# STM32F429_MAIN.net
KiCad netlist of a schematic drawn in Altium Designer
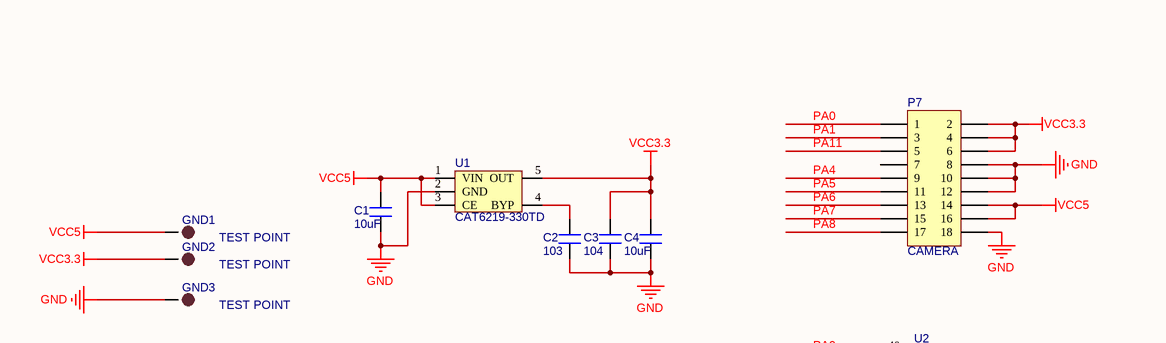
[diagram p0: STM32F429_MAIN.SchDoc, top left]
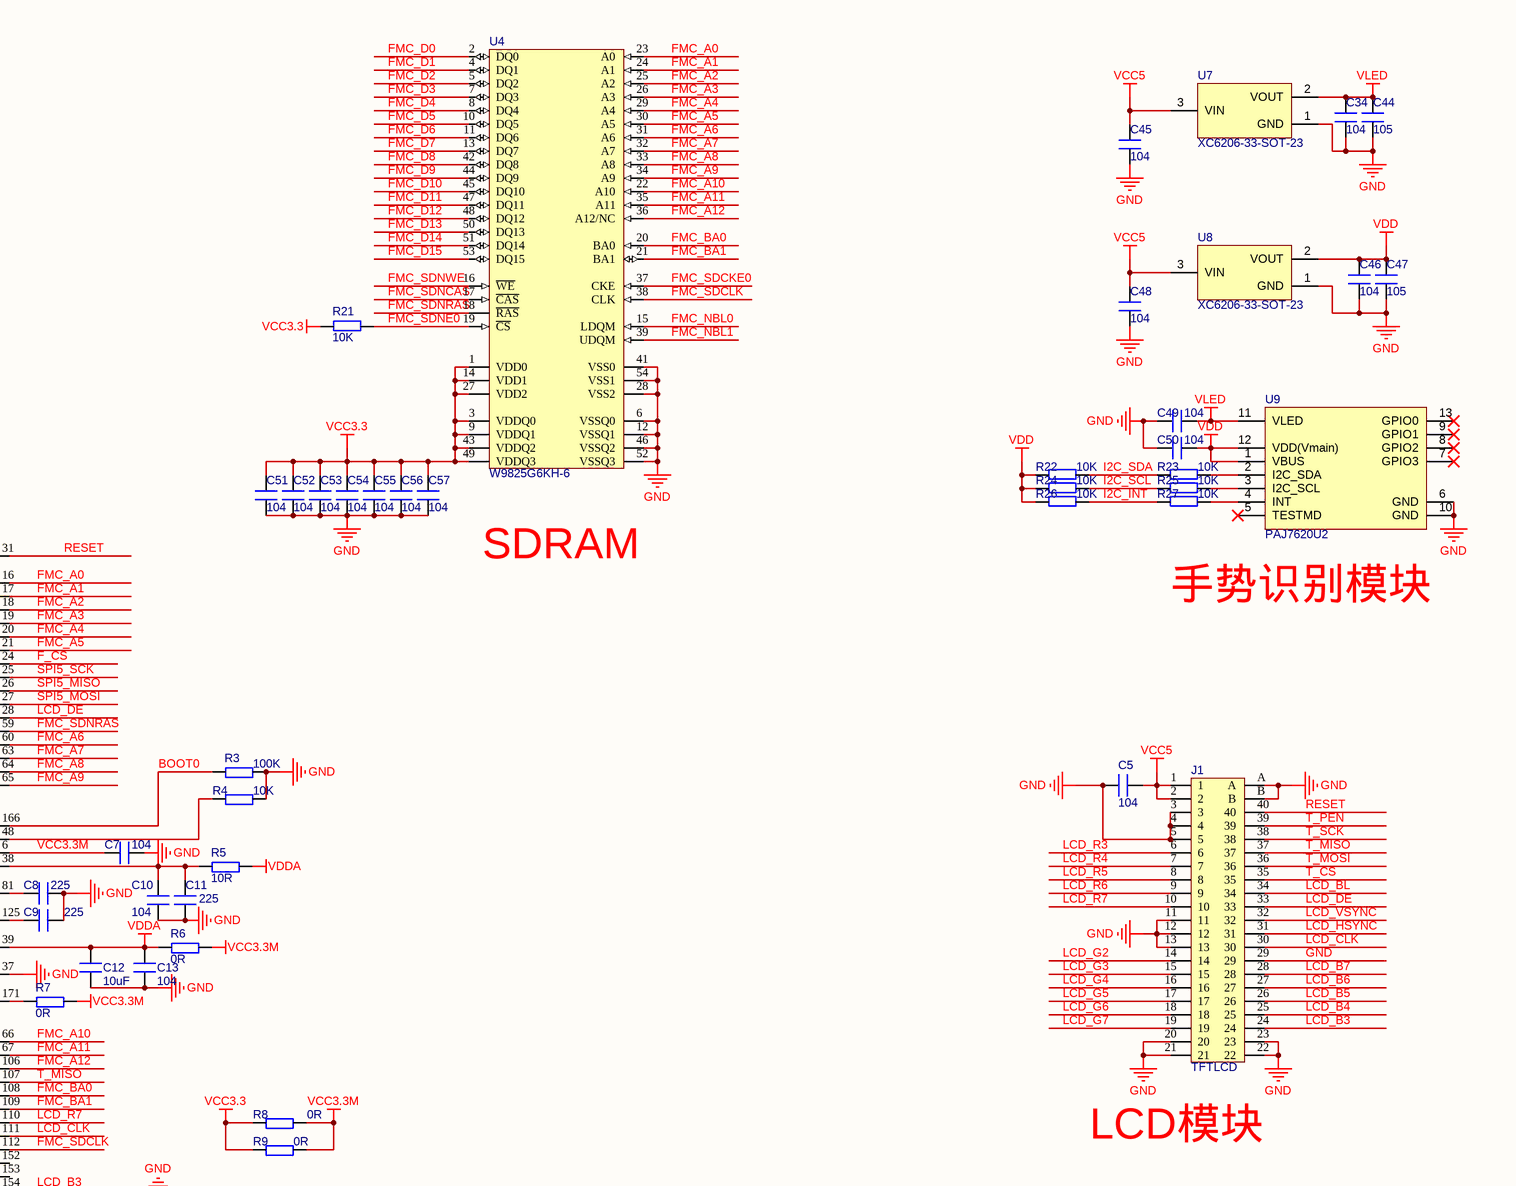
[diagram p1: STM32F429_MAIN.SchDoc, top right]
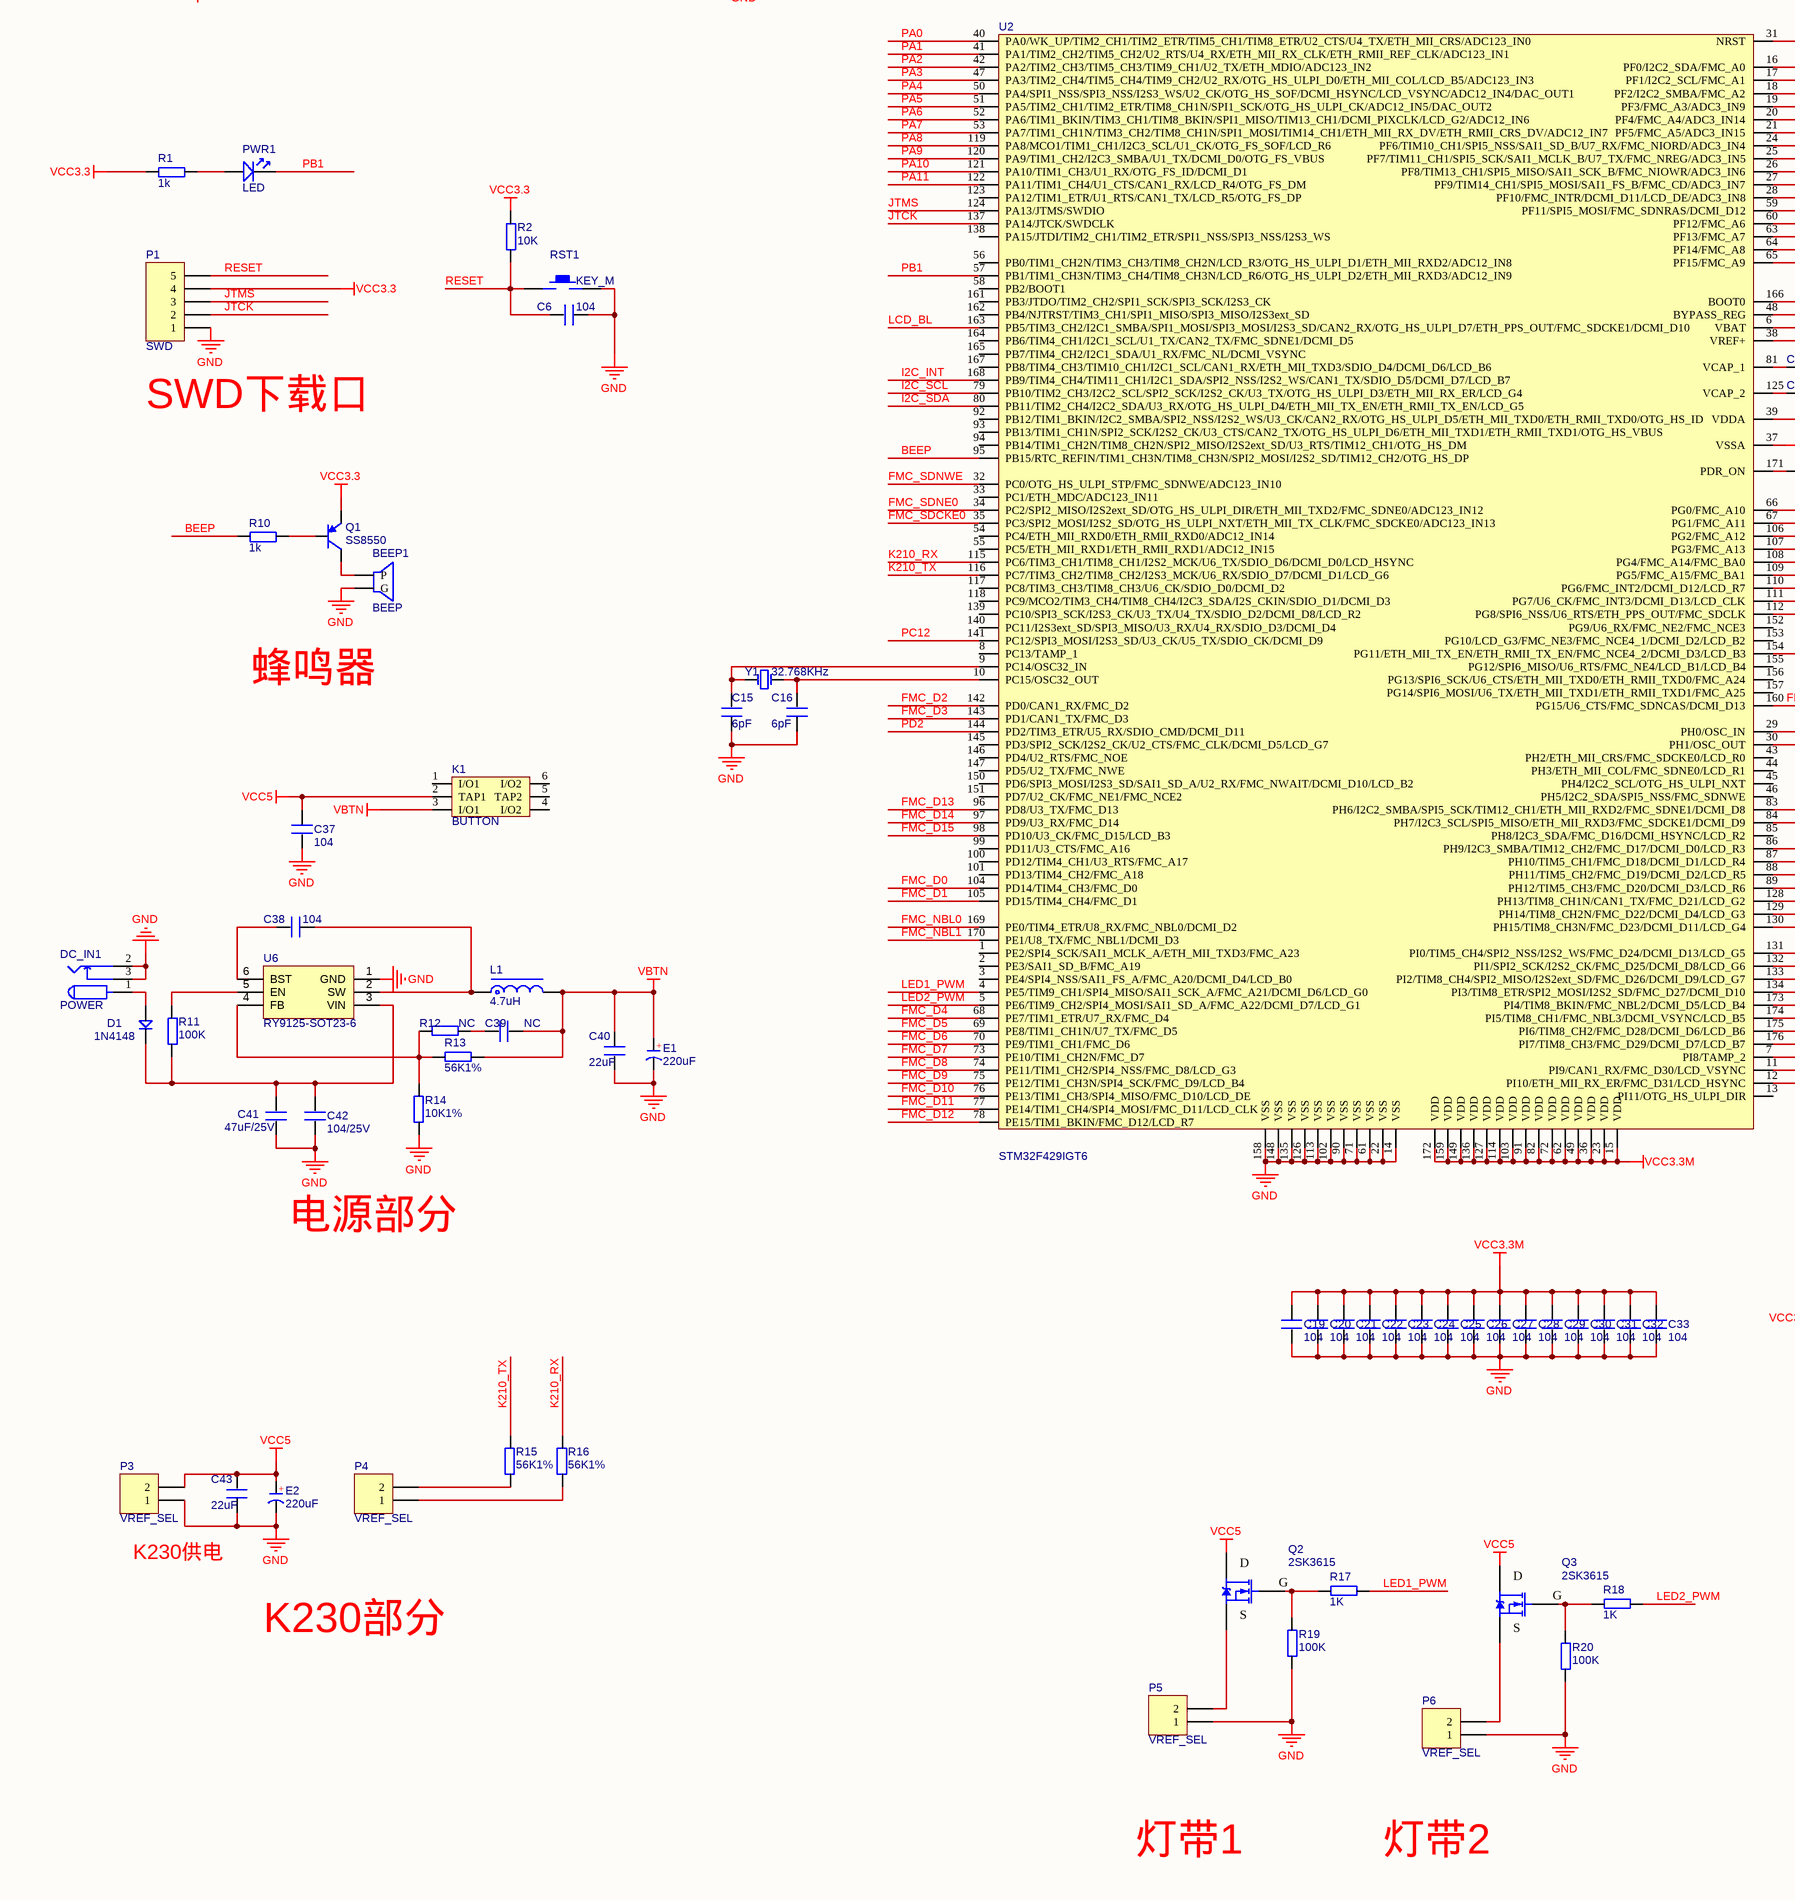
[diagram p2: STM32F429_MAIN.SchDoc, bottom left]
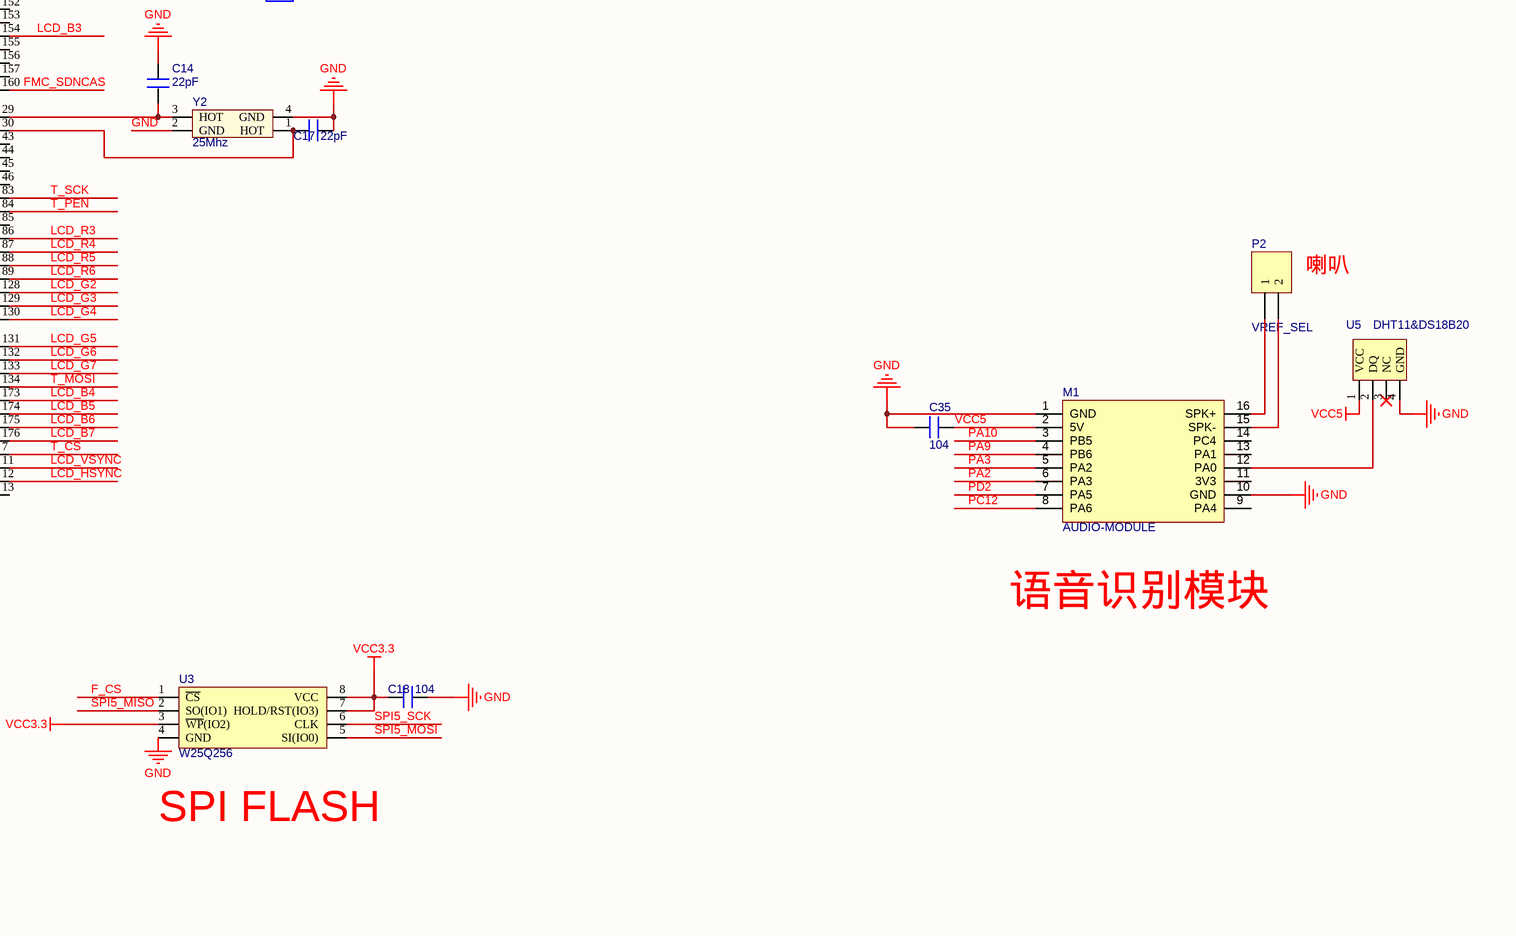
[diagram p3: STM32F429_MAIN.SchDoc, bottom right]

(export (version "E")
  (design (tool "Eeschema 10.0.6"))
  (components
    (comp (ref "BEEP1")
      (value "BEEP")
      (footprint "BELL-5")
      (libsource (lib "阿波罗STM32F4&F7底板封装库") (part "BEEP"))
    )
    (comp (ref "C1") (value "10uF") (footprint "0402") (libsource (lib "STM32F429核心板封装库") (part "C")))
    (comp (ref "C2") (value "103") (footprint "0402") (libsource (lib "STM32F429核心板封装库") (part "C")))
    (comp (ref "C3") (value "104") (footprint "0402") (libsource (lib "STM32F429核心板封装库") (part "C")))
    (comp (ref "C4") (value "10uF") (footprint "0402") (libsource (lib "STM32F429核心板封装库") (part "C")))
    (comp (ref "C5") (value "104") (footprint "0603P") (libsource (lib "ATK-4342 4.3寸RGB屏模块封装库") (part "C")))
    (comp (ref "C6") (value "104") (footprint "0402") (libsource (lib "STM32F429核心板封装库") (part "C")))
    (comp (ref "C7") (value "104") (footprint "0402") (libsource (lib "STM32F429核心板封装库") (part "C")))
    (comp (ref "C8") (value "225") (footprint "0402") (libsource (lib "STM32F429核心板封装库") (part "C")))
    (comp (ref "C9") (value "225") (footprint "0402") (libsource (lib "STM32F429核心板封装库") (part "C")))
    (comp (ref "C10") (value "104") (footprint "0402") (libsource (lib "STM32F429核心板封装库") (part "C")))
    (comp (ref "C11") (value "225") (footprint "0402") (libsource (lib "STM32F429核心板封装库") (part "C")))
    (comp (ref "C12") (value "10uF") (footprint "0402") (libsource (lib "STM32F429核心板封装库") (part "C")))
    (comp (ref "C13") (value "104") (footprint "0402") (libsource (lib "STM32F429核心板封装库") (part "C")))
    (comp (ref "C14") (value "22pF") (footprint "0402") (libsource (lib "STM32F429核心板封装库") (part "C")))
    (comp (ref "C15") (value "6pF") (footprint "0402") (libsource (lib "STM32F429核心板封装库") (part "C")))
    (comp (ref "C16") (value "6pF") (footprint "0402") (libsource (lib "STM32F429核心板封装库") (part "C")))
    (comp (ref "C17") (value "22pF") (footprint "0402") (libsource (lib "STM32F429核心板封装库") (part "C")))
    (comp (ref "C18") (value "104") (footprint "0402") (libsource (lib "STM32F429核心板封装库") (part "C")))
    (comp (ref "C19") (value "104") (footprint "0402") (libsource (lib "STM32F429核心板封装库") (part "C")))
    (comp (ref "C20") (value "104") (footprint "0402") (libsource (lib "STM32F429核心板封装库") (part "C")))
    (comp (ref "C21") (value "104") (footprint "0402") (libsource (lib "STM32F429核心板封装库") (part "C")))
    (comp (ref "C22") (value "104") (footprint "0402") (libsource (lib "STM32F429核心板封装库") (part "C")))
    (comp (ref "C23") (value "104") (footprint "0402") (libsource (lib "STM32F429核心板封装库") (part "C")))
    (comp (ref "C24") (value "104") (footprint "0402") (libsource (lib "STM32F429核心板封装库") (part "C")))
    (comp (ref "C25") (value "104") (footprint "0402") (libsource (lib "STM32F429核心板封装库") (part "C")))
    (comp (ref "C26") (value "104") (footprint "0402") (libsource (lib "STM32F429核心板封装库") (part "C")))
    (comp (ref "C27") (value "104") (footprint "0402") (libsource (lib "STM32F429核心板封装库") (part "C")))
    (comp (ref "C28") (value "104") (footprint "0402") (libsource (lib "STM32F429核心板封装库") (part "C")))
    (comp (ref "C29") (value "104") (footprint "0402") (libsource (lib "STM32F429核心板封装库") (part "C")))
    (comp (ref "C30") (value "104") (footprint "0402") (libsource (lib "STM32F429核心板封装库") (part "C")))
    (comp (ref "C31") (value "104") (footprint "0402") (libsource (lib "STM32F429核心板封装库") (part "C")))
    (comp (ref "C32") (value "104") (footprint "0402") (libsource (lib "STM32F429核心板封装库") (part "C")))
    (comp (ref "C33") (value "104") (footprint "0402") (libsource (lib "STM32F429核心板封装库") (part "C")))
    (comp (ref "C34") (value "104") (footprint "0603P") (libsource (lib "ATK-4342 4.3寸RGB屏模块封装库") (part "C")))
    (comp (ref "C35") (value "104") (footprint "0603P") (libsource (lib "ATK-4342 4.3寸RGB屏模块封装库") (part "C")))
    (comp (ref "C37") (value "104") (footprint "0402") (libsource (lib "STM32F429核心板封装库") (part "C")))
    (comp (ref "C38") (value "104") (footprint "0805") (libsource (lib "STM32F429核心板封装库") (part "C")))
    (comp (ref "C39") (value "NC") (footprint "0603P") (libsource (lib "STM32F429核心板封装库") (part "C")))
    (comp (ref "C40") (value "22uF") (footprint "C 1206_L") (libsource (lib "STM32F429核心板封装库") (part "C")))
    (comp (ref "C41") (value "47uF/25V") (footprint "0805") (libsource (lib "STM32F429核心板封装库") (part "C")))
    (comp (ref "C42") (value "104/25V") (footprint "0805") (libsource (lib "STM32F429核心板封装库") (part "C")))
    (comp (ref "C43") (value "22uF") (footprint "0402") (libsource (lib "STM32F429核心板封装库") (part "C")))
    (comp (ref "C44") (value "105") (footprint "0603P") (libsource (lib "ATK-4342 4.3寸RGB屏模块封装库") (part "C")))
    (comp (ref "C45") (value "104") (footprint "0603P") (libsource (lib "ATK-4342 4.3寸RGB屏模块封装库") (part "C")))
    (comp (ref "C46") (value "104") (footprint "0603P") (libsource (lib "ATK-4342 4.3寸RGB屏模块封装库") (part "C")))
    (comp (ref "C47") (value "105") (footprint "0603P") (libsource (lib "ATK-4342 4.3寸RGB屏模块封装库") (part "C")))
    (comp (ref "C48") (value "104") (footprint "0603P") (libsource (lib "ATK-4342 4.3寸RGB屏模块封装库") (part "C")))
    (comp (ref "C49") (value "104") (footprint "0603P") (libsource (lib "ATK-4342 4.3寸RGB屏模块封装库") (part "C")))
    (comp (ref "C50") (value "104") (footprint "0603P") (libsource (lib "ATK-4342 4.3寸RGB屏模块封装库") (part "C")))
    (comp (ref "C51") (value "104") (footprint "0603P") (libsource (lib "ATK-4342 4.3寸RGB屏模块封装库") (part "C")))
    (comp (ref "C52") (value "104") (footprint "0603P") (libsource (lib "ATK-4342 4.3寸RGB屏模块封装库") (part "C")))
    (comp (ref "C53") (value "104") (footprint "0603P") (libsource (lib "ATK-4342 4.3寸RGB屏模块封装库") (part "C")))
    (comp (ref "C54") (value "104") (footprint "0603P") (libsource (lib "ATK-4342 4.3寸RGB屏模块封装库") (part "C")))
    (comp (ref "C55") (value "104") (footprint "0603P") (libsource (lib "ATK-4342 4.3寸RGB屏模块封装库") (part "C")))
    (comp (ref "C56") (value "104") (footprint "0603P") (libsource (lib "ATK-4342 4.3寸RGB屏模块封装库") (part "C")))
    (comp (ref "C57") (value "104") (footprint "0603P") (libsource (lib "ATK-4342 4.3寸RGB屏模块封装库") (part "C")))
    (comp (ref "D1")
      (value "1N4148")
      (footprint "DIODE_SOP")
      (libsource (lib "阿波罗STM32F4&F7底板封装库") (part "D"))
    )
    (comp (ref "DC_IN1")
      (value "POWER")
      (footprint "DC10B")
      (libsource (lib "阿波罗STM32F4&F7底板封装库") (part "POW"))
    )
    (comp (ref "E1")
      (value "220uF")
      (footprint "CM A(3*5.4)")
      (description "贴片电解电容")
      (fields (field (name "版权归属") "源创客"))
      (libsource (lib "Basic") (part "C-CM"))
    )
    (comp (ref "E2")
      (value "220uF")
      (footprint "CM A(3*5.4)")
      (description "贴片电解电容")
      (fields (field (name "版权归属") "源创客"))
      (libsource (lib "Basic") (part "C-CM"))
    )
    (comp (ref "GND1")
      (value "TEST POINT")
      (footprint "TP-1.5")
      (description "测试点")
      (libsource (lib "STM32F429核心板封装库") (part "TEST-POINT"))
    )
    (comp (ref "GND2")
      (value "TEST POINT")
      (footprint "TP-1.5")
      (description "测试点")
      (libsource (lib "STM32F429核心板封装库") (part "TEST-POINT"))
    )
    (comp (ref "GND3")
      (value "TEST POINT")
      (footprint "TP-1.5")
      (description "测试点")
      (libsource (lib "STM32F429核心板封装库") (part "TEST-POINT"))
    )
    (comp (ref "J1")
      (value "TFTLCD")
      (footprint "FPC-TOP40")
      (description "FPC-40P-0.5mm")
      (libsource (lib "ATK-4342 4.3寸RGB屏模块封装库") (part "FPC-40"))
    )
    (comp (ref "K1")
      (value "BUTTON")
      (footprint "BTN8.5*8.5")
      (libsource (lib "阿波罗STM32F4&F7底板封装库") (part "BUTTON"))
    )
    (comp (ref "L1")
      (value "4.7uH")
      (footprint "CD31")
      (description "贴片功率电感")
      (fields (field (name "版权归属") "源创客"))
      (libsource (lib "Basic") (part "L-CD"))
    )
    (comp (ref "M1")
      (value "AUDIO-MODULE")
      (footprint "AI_audio")
      (libsource (lib "智能导航仪") (part "ai_audio"))
    )
    (comp (ref "P1")
      (value "SWD")
      (footprint "HDR1X5")
      (description "Header, 5-Pin")
      (fields (field (name "PUBLISHER") "Altium Limited"))
      (libsource (lib "STM32F429核心板封装库") (part "Header 5"))
    )
    (comp (ref "P2")
      (value "VREF_SEL")
      (footprint "HDR1X2")
      (description "Header, 2-Pin")
      (fields (field (name "PUBLISHER") "Altium Limited"))
      (libsource (lib "") (part "Header 2_1"))
    )
    (comp (ref "P3")
      (value "VREF_SEL")
      (footprint "HDR1X2")
      (description "Header, 2-Pin")
      (fields (field (name "PUBLISHER") "Altium Limited"))
      (libsource (lib "阿波罗STM32F4&F7底板封装库") (part "Header 2"))
    )
    (comp (ref "P4")
      (value "VREF_SEL")
      (footprint "HDR1X2")
      (description "Header, 2-Pin")
      (fields (field (name "PUBLISHER") "Altium Limited"))
      (libsource (lib "阿波罗STM32F4&F7底板封装库") (part "Header 2"))
    )
    (comp (ref "P5")
      (value "VREF_SEL")
      (footprint "HDR1X2")
      (description "Header, 2-Pin")
      (fields (field (name "PUBLISHER") "Altium Limited"))
      (libsource (lib "阿波罗STM32F4&F7底板封装库") (part "Header 2"))
    )
    (comp (ref "P6")
      (value "VREF_SEL")
      (footprint "HDR1X2")
      (description "Header, 2-Pin")
      (fields (field (name "PUBLISHER") "Altium Limited"))
      (libsource (lib "阿波罗STM32F4&F7底板封装库") (part "Header 2"))
    )
    (comp (ref "P7")
      (value "CAMERA")
      (footprint "HDR2X9")
      (description "Header, 9-Pin, Dual row")
      (fields (field (name "PUBLISHER") "Altium Limited"))
      (libsource (lib "阿波罗STM32F4&F7底板封装库") (part "Header 9X2"))
    )
    (comp (ref "PWR1")
      (value "LED")
      (footprint "SMDLED-0603")
      (libsource (lib "STM32F429核心板封装库") (part "LED"))
    )
    (comp (ref "Q1")
      (value "SS8550")
      (footprint "SOT23-3N")
      (description "高频放大-PNP型")
      (fields (field (name "版权归属") "源创客"))
      (libsource (lib "Basic") (part "8550-SMD"))
    )
    (comp (ref "Q2")
      (value "2SK3615")
      (footprint "TO252")
      (description "N沟场效应管")
      (fields (field (name "版权归属") "源创客"))
      (libsource (lib "Basic") (part "2SK3615"))
    )
    (comp (ref "Q3")
      (value "2SK3615")
      (footprint "TO252")
      (description "N沟场效应管")
      (fields (field (name "版权归属") "源创客"))
      (libsource (lib "Basic") (part "2SK3615"))
    )
    (comp (ref "R1") (value "1k") (footprint "0402") (libsource (lib "STM32F429核心板封装库") (part "R")))
    (comp (ref "R2") (value "10K") (footprint "0402") (libsource (lib "STM32F429核心板封装库") (part "R")))
    (comp (ref "R3") (value "100K") (footprint "0402") (libsource (lib "STM32F429核心板封装库") (part "R")))
    (comp (ref "R4") (value "10K") (footprint "0402") (libsource (lib "STM32F429核心板封装库") (part "R")))
    (comp (ref "R5") (value "10R") (footprint "0402") (libsource (lib "STM32F429核心板封装库") (part "R")))
    (comp (ref "R6") (value "0R") (footprint "0402") (libsource (lib "STM32F429核心板封装库") (part "R")))
    (comp (ref "R7") (value "0R") (footprint "0402") (libsource (lib "STM32F429核心板封装库") (part "R")))
    (comp (ref "R8") (value "0R") (footprint "0402") (libsource (lib "STM32F429核心板封装库") (part "R")))
    (comp (ref "R9") (value "0R") (footprint "0402") (libsource (lib "STM32F429核心板封装库") (part "R")))
    (comp (ref "R10") (value "1k") (footprint "0402") (libsource (lib "STM32F429核心板封装库") (part "R")))
    (comp (ref "R11") (value "100K") (footprint "0603P") (libsource (lib "STM32F429核心板封装库") (part "R")))
    (comp (ref "R12") (value "NC") (footprint "0603P") (libsource (lib "STM32F429核心板封装库") (part "R")))
    (comp (ref "R13") (value "56K1%") (footprint "0603P") (libsource (lib "STM32F429核心板封装库") (part "R")))
    (comp (ref "R14") (value "10K1%") (footprint "0603P") (libsource (lib "STM32F429核心板封装库") (part "R")))
    (comp (ref "R15") (value "56K1%") (footprint "0402") (libsource (lib "STM32F429核心板封装库") (part "R")))
    (comp (ref "R16") (value "56K1%") (footprint "0402") (libsource (lib "STM32F429核心板封装库") (part "R")))
    (comp (ref "R17") (value "1K") (footprint "0603P") (libsource (lib "STM32F429核心板封装库") (part "R")))
    (comp (ref "R18") (value "1K") (footprint "0603P") (libsource (lib "STM32F429核心板封装库") (part "R")))
    (comp (ref "R19") (value "100K") (footprint "0603P") (libsource (lib "STM32F429核心板封装库") (part "R")))
    (comp (ref "R20") (value "100K") (footprint "0603P") (libsource (lib "STM32F429核心板封装库") (part "R")))
    (comp (ref "R21") (value "10K") (footprint "0402") (libsource (lib "STM32F429核心板封装库") (part "R")))
    (comp (ref "R22") (value "10K") (footprint "0402") (libsource (lib "STM32F429核心板封装库") (part "R")))
    (comp (ref "R23") (value "10K") (footprint "0402") (libsource (lib "STM32F429核心板封装库") (part "R")))
    (comp (ref "R24") (value "10K") (footprint "0402") (libsource (lib "STM32F429核心板封装库") (part "R")))
    (comp (ref "R25") (value "10K") (footprint "0402") (libsource (lib "STM32F429核心板封装库") (part "R")))
    (comp (ref "R26") (value "10K") (footprint "0402") (libsource (lib "STM32F429核心板封装库") (part "R")))
    (comp (ref "R27") (value "10K") (footprint "0402") (libsource (lib "STM32F429核心板封装库") (part "R")))
    (comp (ref "RST1")
      (value "KEY_M")
      (footprint "KEY_SOP3625")
      (libsource (lib "STM32F429核心板封装库") (part "KEY_M"))
    )
    (comp (ref "U1")
      (value "CAT6219-330TD")
      (footprint "SOT-23-5")
      (description "3.3V 500mA LDO")
      (libsource (lib "STM32F429核心板封装库") (part "CAT6219-330TD"))
    )
    (comp (ref "U2")
      (value "STM32F429IGT6")
      (footprint "LQFP176")
      (libsource (lib "STM32F429核心板封装库") (part "STM32F429IGT6"))
    )
    (comp (ref "U3")
      (value "W25Q256")
      (footprint "WSON8")
      (description "W25Q128")
      (libsource (lib "STM32F429核心板封装库") (part "W25Q128"))
    )
    (comp (ref "U4")
      (value "W9825G6KH-6")
      (footprint "TSOP54")
      (description "32MB SDRAM")
      (libsource (lib "STM32F429核心板封装库") (part "IS42S16160B"))
    )
    (comp (ref "U5")
      (value "DHT11&DS18B20")
      (footprint "DHT11")
      (description "数字温湿度传感器")
      (libsource (lib "阿波罗STM32F4&F7底板封装库") (part "DHT11"))
    )
    (comp (ref "U6") (value "RY9125-SOT23-6") (footprint "SOT23-6") (libsource (lib "智能导航仪") (part "RY9125")))
    (comp (ref "U7")
      (value "XC6206-33-SOT-23")
      (footprint "SOT-23")
      (libsource (lib "智能导航仪") (part "XC6206-33"))
    )
    (comp (ref "U8")
      (value "XC6206-33-SOT-23")
      (footprint "SOT-23")
      (libsource (lib "智能导航仪") (part "XC6206-33"))
    )
    (comp (ref "U9") (value "PAJ7620U2") (footprint "PAJ7620U2") (libsource (lib "智能导航仪") (part "PAJ7620U2")))
    (comp (ref "Y1")
      (value "32.768KHz")
      (footprint "XTAL3215")
      (description "普通晶振")
      (fields (field (name "PUBLISHER") "Altium Limited"))
      (libsource (lib "STM32F429核心板封装库") (part "XTAL"))
    )
    (comp (ref "Y2")
      (value "25Mhz")
      (footprint "XTAL3225")
      (description "3225贴片无源晶振")
      (libsource (lib "STM32F429核心板封装库") (part "XTAL_3225"))
    )
  )
  (nets
    (net (code "1") (name "/BEEP") (class "Default")
      (node (ref "R10") (pin "1") (pintype "passive"))
      (node (ref "U2") (pin "95") (pinfunction "PB15/RTC_REFIN/TIM1_CH3N/TIM8_CH3N/SPI2_MOSI/I2S2_SD/TIM12_CH2/OTG_HS_DP_95") (pintype "passive"))
    )
    (net (code "2") (name "/BOOT0") (class "Default")
      (node (ref "R3") (pin "1") (pintype "passive"))
      (node (ref "U2") (pin "166") (pinfunction "BOOT0_166") (pintype "passive"))
    )
    (net (code "3") (name "/FMC_A0") (class "Default")
      (node (ref "U2") (pin "16") (pinfunction "PF0/I2C2_SDA/FMC_A0_16") (pintype "passive"))
      (node (ref "U4") (pin "23") (pinfunction "A0_23") (pintype "input"))
    )
    (net (code "4") (name "/FMC_A1") (class "Default")
      (node (ref "U2") (pin "17") (pinfunction "PF1/I2C2_SCL/FMC_A1_17") (pintype "passive"))
      (node (ref "U4") (pin "24") (pinfunction "A1_24") (pintype "input"))
    )
    (net (code "5") (name "/FMC_A2") (class "Default")
      (node (ref "U2") (pin "18") (pinfunction "PF2/I2C2_SMBA/FMC_A2_18") (pintype "passive"))
      (node (ref "U4") (pin "25") (pinfunction "A2_25") (pintype "input"))
    )
    (net (code "6") (name "/FMC_A3") (class "Default")
      (node (ref "U2") (pin "19") (pinfunction "PF3/FMC_A3/ADC3_IN9_19") (pintype "passive"))
      (node (ref "U4") (pin "26") (pinfunction "A3_26") (pintype "input"))
    )
    (net (code "7") (name "/FMC_A4") (class "Default")
      (node (ref "U2") (pin "20") (pinfunction "PF4/FMC_A4/ADC3_IN14_20") (pintype "passive"))
      (node (ref "U4") (pin "29") (pinfunction "A4_29") (pintype "input"))
    )
    (net (code "8") (name "/FMC_A5") (class "Default")
      (node (ref "U2") (pin "21") (pinfunction "PF5/FMC_A5/ADC3_IN15_21") (pintype "passive"))
      (node (ref "U4") (pin "30") (pinfunction "A5_30") (pintype "input"))
    )
    (net (code "9") (name "/FMC_A6") (class "Default")
      (node (ref "U2") (pin "60") (pinfunction "PF12/FMC_A6_60") (pintype "passive"))
      (node (ref "U4") (pin "31") (pinfunction "A6_31") (pintype "input"))
    )
    (net (code "10") (name "/FMC_A7") (class "Default")
      (node (ref "U2") (pin "63") (pinfunction "PF13/FMC_A7_63") (pintype "passive"))
      (node (ref "U4") (pin "32") (pinfunction "A7_32") (pintype "input"))
    )
    (net (code "11") (name "/FMC_A8") (class "Default")
      (node (ref "U2") (pin "64") (pinfunction "PF14/FMC_A8_64") (pintype "passive"))
      (node (ref "U4") (pin "33") (pinfunction "A8_33") (pintype "input"))
    )
    (net (code "12") (name "/FMC_A9") (class "Default")
      (node (ref "U2") (pin "65") (pinfunction "PF15/FMC_A9_65") (pintype "passive"))
      (node (ref "U4") (pin "34") (pinfunction "A9_34") (pintype "input"))
    )
    (net (code "13") (name "/FMC_A10") (class "Default")
      (node (ref "U2") (pin "66") (pinfunction "PG0/FMC_A10_66") (pintype "passive"))
      (node (ref "U4") (pin "22") (pinfunction "A10_22") (pintype "input"))
    )
    (net (code "14") (name "/FMC_A11") (class "Default")
      (node (ref "U2") (pin "67") (pinfunction "PG1/FMC_A11_67") (pintype "passive"))
      (node (ref "U4") (pin "35") (pinfunction "A11_35") (pintype "input"))
    )
    (net (code "15") (name "/FMC_A12") (class "Default")
      (node (ref "U2") (pin "106") (pinfunction "PG2/FMC_A12_106") (pintype "passive"))
      (node (ref "U4") (pin "36") (pinfunction "A12/NC_36") (pintype "input"))
    )
    (net (code "16") (name "/FMC_BA0") (class "Default")
      (node (ref "U2") (pin "108") (pinfunction "PG4/FMC_A14/FMC_BA0_108") (pintype "passive"))
      (node (ref "U4") (pin "20") (pinfunction "BA0_20") (pintype "input"))
    )
    (net (code "17") (name "/FMC_BA1") (class "Default")
      (node (ref "U2") (pin "109") (pinfunction "PG5/FMC_A15/FMC_BA1_109") (pintype "passive"))
      (node (ref "U4") (pin "21") (pinfunction "BA1_21") (pintype "bidirectional"))
    )
    (net (code "18") (name "/FMC_D0") (class "Default")
      (node (ref "U2") (pin "104") (pinfunction "PD14/TIM4_CH3/FMC_D0_104") (pintype "passive"))
      (node (ref "U4") (pin "2") (pinfunction "DQ0_2") (pintype "bidirectional"))
    )
    (net (code "19") (name "/FMC_D1") (class "Default")
      (node (ref "U2") (pin "105") (pinfunction "PD15/TIM4_CH4/FMC_D1_105") (pintype "passive"))
      (node (ref "U4") (pin "4") (pinfunction "DQ1_4") (pintype "bidirectional"))
    )
    (net (code "20") (name "/FMC_D2") (class "Default")
      (node (ref "U2") (pin "142") (pinfunction "PD0/CAN1_RX/FMC_D2_142") (pintype "passive"))
      (node (ref "U4") (pin "5") (pinfunction "DQ2_5") (pintype "bidirectional"))
    )
    (net (code "21") (name "/FMC_D3") (class "Default")
      (node (ref "U2") (pin "143") (pinfunction "PD1/CAN1_TX/FMC_D3_143") (pintype "passive"))
      (node (ref "U4") (pin "7") (pinfunction "DQ3_7") (pintype "bidirectional"))
    )
    (net (code "22") (name "/FMC_D4") (class "Default")
      (node (ref "U2") (pin "68") (pinfunction "PE7/TIM1_ETR/U7_RX/FMC_D4_68") (pintype "passive"))
      (node (ref "U4") (pin "8") (pinfunction "DQ4_8") (pintype "bidirectional"))
    )
    (net (code "23") (name "/FMC_D5") (class "Default")
      (node (ref "U2") (pin "69") (pinfunction "PE8/TIM1_CH1N/U7_TX/FMC_D5_69") (pintype "passive"))
      (node (ref "U4") (pin "10") (pinfunction "DQ5_10") (pintype "bidirectional"))
    )
    (net (code "24") (name "/FMC_D6") (class "Default")
      (node (ref "U2") (pin "70") (pinfunction "PE9/TIM1_CH1/FMC_D6_70") (pintype "passive"))
      (node (ref "U4") (pin "11") (pinfunction "DQ6_11") (pintype "bidirectional"))
    )
    (net (code "25") (name "/FMC_D7") (class "Default")
      (node (ref "U2") (pin "73") (pinfunction "PE10/TIM1_CH2N/FMC_D7_73") (pintype "passive"))
      (node (ref "U4") (pin "13") (pinfunction "DQ7_13") (pintype "bidirectional"))
    )
    (net (code "26") (name "/FMC_D8") (class "Default")
      (node (ref "U2") (pin "74") (pinfunction "PE11/TIM1_CH2/SPI4_NSS/FMC_D8/LCD_G3_74") (pintype "passive"))
      (node (ref "U4") (pin "42") (pinfunction "DQ8_42") (pintype "bidirectional"))
    )
    (net (code "27") (name "/FMC_D9") (class "Default")
      (node (ref "U2") (pin "75") (pinfunction "PE12/TIM1_CH3N/SPI4_SCK/FMC_D9/LCD_B4_75") (pintype "passive"))
      (node (ref "U4") (pin "44") (pinfunction "DQ9_44") (pintype "bidirectional"))
    )
    (net (code "28") (name "/FMC_D10") (class "Default")
      (node (ref "U2") (pin "76") (pinfunction "PE13/TIM1_CH3/SPI4_MISO/FMC_D10/LCD_DE_76") (pintype "passive"))
      (node (ref "U4") (pin "45") (pinfunction "DQ10_45") (pintype "bidirectional"))
    )
    (net (code "29") (name "/FMC_D11") (class "Default")
      (node (ref "U2") (pin "77") (pinfunction "PE14/TIM1_CH4/SPI4_MOSI/FMC_D11/LCD_CLK_77") (pintype "passive"))
      (node (ref "U4") (pin "47") (pinfunction "DQ11_47") (pintype "bidirectional"))
    )
    (net (code "30") (name "/FMC_D12") (class "Default")
      (node (ref "U2") (pin "78") (pinfunction "PE15/TIM1_BKIN/FMC_D12/LCD_R7_78") (pintype "passive"))
      (node (ref "U4") (pin "48") (pinfunction "DQ12_48") (pintype "bidirectional"))
    )
    (net (code "31") (name "/FMC_D13") (class "Default")
      (node (ref "U2") (pin "96") (pinfunction "PD8/U3_TX/FMC_D13_96") (pintype "passive"))
      (node (ref "U4") (pin "50") (pinfunction "DQ13_50") (pintype "bidirectional"))
    )
    (net (code "32") (name "/FMC_D14") (class "Default")
      (node (ref "U2") (pin "97") (pinfunction "PD9/U3_RX/FMC_D14_97") (pintype "passive"))
      (node (ref "U4") (pin "51") (pinfunction "DQ14_51") (pintype "bidirectional"))
    )
    (net (code "33") (name "/FMC_D15") (class "Default")
      (node (ref "U2") (pin "98") (pinfunction "PD10/U3_CK/FMC_D15/LCD_B3_98") (pintype "passive"))
      (node (ref "U4") (pin "53") (pinfunction "DQ15_53") (pintype "bidirectional"))
    )
    (net (code "34") (name "/FMC_NBL0") (class "Default")
      (node (ref "U2") (pin "169") (pinfunction "PE0/TIM4_ETR/U8_RX/FMC_NBL0/DCMI_D2_169") (pintype "passive"))
      (node (ref "U4") (pin "15") (pinfunction "LDQM_15") (pintype "input"))
    )
    (net (code "35") (name "/FMC_NBL1") (class "Default")
      (node (ref "U2") (pin "170") (pinfunction "PE1/U8_TX/FMC_NBL1/DCMI_D3_170") (pintype "passive"))
      (node (ref "U4") (pin "39") (pinfunction "UDQM_39") (pintype "input"))
    )
    (net (code "36") (name "/FMC_SDCKE0") (class "Default")
      (node (ref "U2") (pin "35") (pinfunction "PC3/SPI2_MOSI/I2S2_SD/OTG_HS_ULPI_NXT/ETH_MII_TX_CLK/FMC_SDCKE0/ADC123_IN13_35") (pintype "passive"))
      (node (ref "U4") (pin "37") (pinfunction "CKE_37") (pintype "input"))
    )
    (net (code "37") (name "/FMC_SDCLK") (class "Default")
      (node (ref "U2") (pin "112") (pinfunction "PG8/SPI6_NSS/U6_RTS/ETH_PPS_OUT/FMC_SDCLK_112") (pintype "passive"))
      (node (ref "U4") (pin "38") (pinfunction "CLK_38") (pintype "input"))
    )
    (net (code "38") (name "/FMC_SDNCAS") (class "Default")
      (node (ref "U2") (pin "160") (pinfunction "PG15/U6_CTS/FMC_SDNCAS/DCMI_D13_160") (pintype "passive"))
      (node (ref "U4") (pin "17") (pinfunction "~{CAS}_17") (pintype "input"))
    )
    (net (code "39") (name "/FMC_SDNE0") (class "Default")
      (node (ref "R21") (pin "1") (pintype "passive"))
      (node (ref "U2") (pin "34") (pinfunction "PC2/SPI2_MISO/I2S2ext_SD/OTG_HS_ULPI_DIR/ETH_MII_TXD2/FMC_SDNE0/ADC123_IN12_34") (pintype "passive"))
      (node (ref "U4") (pin "19") (pinfunction "~{CS}_19") (pintype "input"))
    )
    (net (code "40") (name "/FMC_SDNRAS") (class "Default")
      (node (ref "U2") (pin "59") (pinfunction "PF11/SPI5_MOSI/FMC_SDNRAS/DCMI_D12_59") (pintype "passive"))
      (node (ref "U4") (pin "18") (pinfunction "~{RAS}_18") (pintype "passive"))
    )
    (net (code "41") (name "/FMC_SDNWE") (class "Default")
      (node (ref "U2") (pin "32") (pinfunction "PC0/OTG_HS_ULPI_STP/FMC_SDNWE/ADC123_IN10_32") (pintype "passive"))
      (node (ref "U4") (pin "16") (pinfunction "~{WE}_16") (pintype "input"))
    )
    (net (code "42") (name "/F_CS") (class "Default")
      (node (ref "U2") (pin "24") (pinfunction "PF6/TIM10_CH1/SPI5_NSS/SAI1_SD_B/U7_RX/FMC_NIORD/ADC3_IN4_24") (pintype "passive"))
      (node (ref "U3") (pin "1") (pinfunction "~{CS}_1") (pintype "passive"))
    )
    (net (code "43") (name "/I2C_INT") (class "Default")
      (node (ref "R26") (pin "1") (pintype "passive"))
      (node (ref "R27") (pin "2") (pintype "passive"))
      (node (ref "U2") (pin "168") (pinfunction "PB9/TIM4_CH4/TIM11_CH1/I2C1_SDA/SPI2_NSS/I2S2_WS/CAN1_TX/SDIO_D5/DCMI_D7/LCD_B7_168") (pintype "passive"))
    )
    (net (code "44") (name "/I2C_SCL") (class "Default")
      (node (ref "R24") (pin "1") (pintype "passive"))
      (node (ref "R25") (pin "2") (pintype "passive"))
      (node (ref "U2") (pin "79") (pinfunction "PB10/TIM2_CH3/I2C2_SCL/SPI2_SCK/I2S2_CK/U3_TX/OTG_HS_ULPI_D3/ETH_MII_RX_ER/LCD_G4_79") (pintype "passive"))
    )
    (net (code "45") (name "/I2C_SDA") (class "Default")
      (node (ref "R22") (pin "1") (pintype "passive"))
      (node (ref "R23") (pin "2") (pintype "passive"))
      (node (ref "U2") (pin "80") (pinfunction "PB11/TIM2_CH4/I2C2_SDA/U3_RX/OTG_HS_ULPI_D4/ETH_MII_TX_EN/ETH_RMII_TX_EN/LCD_G5_80") (pintype "passive"))
    )
    (net (code "46") (name "/JTCK") (class "Default")
      (node (ref "P1") (pin "2") (pinfunction "2_2") (pintype "passive"))
      (node (ref "U2") (pin "137") (pinfunction "PA14/JTCK/SWDCLK_137") (pintype "passive"))
    )
    (net (code "47") (name "/JTMS") (class "Default")
      (node (ref "P1") (pin "3") (pinfunction "3_3") (pintype "passive"))
      (node (ref "U2") (pin "124") (pinfunction "PA13/JTMS/SWDIO_124") (pintype "passive"))
    )
    (net (code "48") (name "/K210_RX") (class "Default")
      (node (ref "R16") (pin "1") (pintype "passive"))
      (node (ref "U2") (pin "115") (pinfunction "PC6/TIM3_CH1/TIM8_CH1/I2S2_MCK/U6_TX/SDIO_D6/DCMI_D0/LCD_HSYNC_115") (pintype "passive"))
    )
    (net (code "49") (name "/K210_TX") (class "Default")
      (node (ref "R15") (pin "1") (pintype "passive"))
      (node (ref "U2") (pin "116") (pinfunction "PC7/TIM3_CH2/TIM8_CH2/I2S3_MCK/U6_RX/SDIO_D7/DCMI_D1/LCD_G6_116") (pintype "passive"))
    )
    (net (code "50") (name "/LCD_B3") (class "Default")
      (node (ref "J1") (pin "24") (pinfunction "24_24") (pintype "passive"))
      (node (ref "U2") (pin "154") (pinfunction "PG11/ETH_MII_TX_EN/ETH_RMII_TX_EN/FMC_NCE4_2/DCMI_D3/LCD_B3_154") (pintype "passive"))
    )
    (net (code "51") (name "/LCD_B4") (class "Default")
      (node (ref "J1") (pin "25") (pinfunction "25_25") (pintype "passive"))
      (node (ref "U2") (pin "173") (pinfunction "PI4/TIM8_BKIN/FMC_NBL2/DCMI_D5/LCD_B4_173") (pintype "passive"))
    )
    (net (code "52") (name "/LCD_B5") (class "Default")
      (node (ref "J1") (pin "26") (pinfunction "26_26") (pintype "passive"))
      (node (ref "U2") (pin "174") (pinfunction "PI5/TIM8_CH1/FMC_NBL3/DCMI_VSYNC/LCD_B5_174") (pintype "passive"))
    )
    (net (code "53") (name "/LCD_B6") (class "Default")
      (node (ref "J1") (pin "27") (pinfunction "27_27") (pintype "passive"))
      (node (ref "U2") (pin "175") (pinfunction "PI6/TIM8_CH2/FMC_D28/DCMI_D6/LCD_B6_175") (pintype "passive"))
    )
    (net (code "54") (name "/LCD_B7") (class "Default")
      (node (ref "J1") (pin "28") (pinfunction "28_28") (pintype "passive"))
      (node (ref "U2") (pin "176") (pinfunction "PI7/TIM8_CH3/FMC_D29/DCMI_D7/LCD_B7_176") (pintype "passive"))
    )
    (net (code "55") (name "/LCD_BL") (class "Default")
      (node (ref "J1") (pin "34") (pinfunction "34_34") (pintype "passive"))
      (node (ref "U2") (pin "163") (pinfunction "PB5/TIM3_CH2/I2C1_SMBA/SPI1_MOSI/SPI3_MOSI/I2S3_SD/CAN2_RX/OTG_HS_ULPI_D7/ETH_PPS_OUT/FMC_SDCKE1/DCMI_D10_163") (pintype "passive"))
    )
    (net (code "56") (name "/LCD_CLK") (class "Default")
      (node (ref "J1") (pin "30") (pinfunction "30_30") (pintype "passive"))
      (node (ref "U2") (pin "111") (pinfunction "PG7/U6_CK/FMC_INT3/DCMI_D13/LCD_CLK_111") (pintype "passive"))
    )
    (net (code "57") (name "/LCD_DE") (class "Default")
      (node (ref "J1") (pin "33") (pinfunction "33_33") (pintype "passive"))
      (node (ref "U2") (pin "28") (pinfunction "PF10/FMC_INTR/DCMI_D11/LCD_DE/ADC3_IN8_28") (pintype "passive"))
    )
    (net (code "58") (name "/LCD_G2") (class "Default")
      (node (ref "J1") (pin "14") (pinfunction "14_14") (pintype "passive"))
      (node (ref "U2") (pin "128") (pinfunction "PH13/TIM8_CH1N/CAN1_TX/FMC_D21/LCD_G2_128") (pintype "passive"))
    )
    (net (code "59") (name "/LCD_G3") (class "Default")
      (node (ref "J1") (pin "15") (pinfunction "15_15") (pintype "passive"))
      (node (ref "U2") (pin "129") (pinfunction "PH14/TIM8_CH2N/FMC_D22/DCMI_D4/LCD_G3_129") (pintype "passive"))
    )
    (net (code "60") (name "/LCD_G4") (class "Default")
      (node (ref "J1") (pin "16") (pinfunction "16_16") (pintype "passive"))
      (node (ref "U2") (pin "130") (pinfunction "PH15/TIM8_CH3N/FMC_D23/DCMI_D11/LCD_G4_130") (pintype "passive"))
    )
    (net (code "61") (name "/LCD_G5") (class "Default")
      (node (ref "J1") (pin "17") (pinfunction "17_17") (pintype "passive"))
      (node (ref "U2") (pin "131") (pinfunction "PI0/TIM5_CH4/SPI2_NSS/I2S2_WS/FMC_D24/DCMI_D13/LCD_G5_131") (pintype "passive"))
    )
    (net (code "62") (name "/LCD_G6") (class "Default")
      (node (ref "J1") (pin "18") (pinfunction "18_18") (pintype "passive"))
      (node (ref "U2") (pin "132") (pinfunction "PI1/SPI2_SCK/I2S2_CK/FMC_D25/DCMI_D8/LCD_G6_132") (pintype "passive"))
    )
    (net (code "63") (name "/LCD_G7") (class "Default")
      (node (ref "J1") (pin "19") (pinfunction "19_19") (pintype "passive"))
      (node (ref "U2") (pin "133") (pinfunction "PI2/TIM8_CH4/SPI2_MISO/I2S2ext_SD/FMC_D26/DCMI_D9/LCD_G7_133") (pintype "passive"))
    )
    (net (code "64") (name "/LCD_HSYNC") (class "Default")
      (node (ref "J1") (pin "31") (pinfunction "31_31") (pintype "passive"))
      (node (ref "U2") (pin "12") (pinfunction "PI10/ETH_MII_RX_ER/FMC_D31/LCD_HSYNC_12") (pintype "passive"))
    )
    (net (code "65") (name "/LCD_R3") (class "Default")
      (node (ref "J1") (pin "6") (pinfunction "6_6") (pintype "passive"))
      (node (ref "U2") (pin "86") (pinfunction "PH9/I2C3_SMBA/TIM12_CH2/FMC_D17/DCMI_D0/LCD_R3_86") (pintype "passive"))
    )
    (net (code "66") (name "/LCD_R4") (class "Default")
      (node (ref "J1") (pin "7") (pinfunction "7_7") (pintype "passive"))
      (node (ref "U2") (pin "87") (pinfunction "PH10/TIM5_CH1/FMC_D18/DCMI_D1/LCD_R4_87") (pintype "passive"))
    )
    (net (code "67") (name "/LCD_R5") (class "Default")
      (node (ref "J1") (pin "8") (pinfunction "8_8") (pintype "passive"))
      (node (ref "U2") (pin "88") (pinfunction "PH11/TIM5_CH2/FMC_D19/DCMI_D2/LCD_R5_88") (pintype "passive"))
    )
    (net (code "68") (name "/LCD_R6") (class "Default")
      (node (ref "J1") (pin "9") (pinfunction "9_9") (pintype "passive"))
      (node (ref "U2") (pin "89") (pinfunction "PH12/TIM5_CH3/FMC_D20/DCMI_D3/LCD_R6_89") (pintype "passive"))
    )
    (net (code "69") (name "/LCD_R7") (class "Default")
      (node (ref "J1") (pin "10") (pinfunction "10_10") (pintype "passive"))
      (node (ref "U2") (pin "110") (pinfunction "PG6/FMC_INT2/DCMI_D12/LCD_R7_110") (pintype "passive"))
    )
    (net (code "70") (name "/LCD_VSYNC") (class "Default")
      (node (ref "J1") (pin "32") (pinfunction "32_32") (pintype "passive"))
      (node (ref "U2") (pin "11") (pinfunction "PI9/CAN1_RX/FMC_D30/LCD_VSYNC_11") (pintype "passive"))
    )
    (net (code "71") (name "/LED1_PWM") (class "Default")
      (node (ref "R17") (pin "1") (pintype "passive"))
      (node (ref "U2") (pin "4") (pinfunction "PE5/TIM9_CH1/SPI4_MISO/SAI1_SCK_A/FMC_A21/DCMI_D6/LCD_G0_4") (pintype "passive"))
    )
    (net (code "72") (name "/LED2_PWM") (class "Default")
      (node (ref "R18") (pin "1") (pintype "passive"))
      (node (ref "U2") (pin "5") (pinfunction "PE6/TIM9_CH2/SPI4_MOSI/SAI1_SD_A/FMC_A22/DCMI_D7/LCD_G1_5") (pintype "passive"))
    )
    (net (code "73") (name "/PA0") (class "Default")
      (node (ref "P7") (pin "1") (pinfunction "1_1") (pintype "passive"))
      (node (ref "U2") (pin "40") (pinfunction "PA0/WK_UP/TIM2_CH1/TIM2_ETR/TIM5_CH1/TIM8_ETR/U2_CTS/U4_TX/ETH_MII_CRS/ADC123_IN0_40") (pintype "passive"))
    )
    (net (code "74") (name "/PA1") (class "Default")
      (node (ref "P7") (pin "3") (pinfunction "3_3") (pintype "passive"))
      (node (ref "U2") (pin "41") (pinfunction "PA1/TIM2_CH2/TIM5_CH2/U2_RTS/U4_RX/ETH_MII_RX_CLK/ETH_RMII_REF_CLK/ADC123_IN1_41") (pintype "passive"))
    )
    (net (code "75") (name "/PA2") (class "Default")
      (node (ref "M1") (pin "6") (pinfunction "PA3_6") (pintype "passive"))
      (node (ref "U2") (pin "42") (pinfunction "PA2/TIM2_CH3/TIM5_CH3/TIM9_CH1/U2_TX/ETH_MDIO/ADC123_IN2_42") (pintype "passive"))
    )
    (net (code "76") (name "/PA3") (class "Default")
      (node (ref "M1") (pin "5") (pinfunction "PA2_5") (pintype "passive"))
      (node (ref "U2") (pin "47") (pinfunction "PA3/TIM2_CH4/TIM5_CH4/TIM9_CH2/U2_RX/OTG_HS_ULPI_D0/ETH_MII_COL/LCD_B5/ADC123_IN3_47") (pintype "passive"))
    )
    (net (code "77") (name "/PA4") (class "Default")
      (node (ref "P7") (pin "9") (pinfunction "9_9") (pintype "passive"))
      (node (ref "U2") (pin "50") (pinfunction "PA4/SPI1_NSS/SPI3_NSS/I2S3_WS/U2_CK/OTG_HS_SOF/DCMI_HSYNC/LCD_VSYNC/ADC12_IN4/DAC_OUT1_50") (pintype "passive"))
    )
    (net (code "78") (name "/PA5") (class "Default")
      (node (ref "P7") (pin "11") (pinfunction "11_11") (pintype "passive"))
      (node (ref "U2") (pin "51") (pinfunction "PA5/TIM2_CH1/TIM2_ETR/TIM8_CH1N/SPI1_SCK/OTG_HS_ULPI_CK/ADC12_IN5/DAC_OUT2_51") (pintype "passive"))
    )
    (net (code "79") (name "/PA6") (class "Default")
      (node (ref "P7") (pin "13") (pinfunction "13_13") (pintype "passive"))
      (node (ref "U2") (pin "52") (pinfunction "PA6/TIM1_BKIN/TIM3_CH1/TIM8_BKIN/SPI1_MISO/TIM13_CH1/DCMI_PIXCLK/LCD_G2/ADC12_IN6_52") (pintype "passive"))
    )
    (net (code "80") (name "/PA7") (class "Default")
      (node (ref "P7") (pin "15") (pinfunction "15_15") (pintype "passive"))
      (node (ref "U2") (pin "53") (pinfunction "PA7/TIM1_CH1N/TIM3_CH2/TIM8_CH1N/SPI1_MOSI/TIM14_CH1/ETH_MII_RX_DV/ETH_RMII_CRS_DV/ADC12_IN7_53") (pintype "passive"))
    )
    (net (code "81") (name "/PA8") (class "Default")
      (node (ref "P7") (pin "17") (pinfunction "17_17") (pintype "passive"))
      (node (ref "U2") (pin "119") (pinfunction "PA8/MCO1/TIM1_CH1/I2C3_SCL/U1_CK/OTG_FS_SOF/LCD_R6_119") (pintype "passive"))
    )
    (net (code "82") (name "/PA9") (class "Default")
      (node (ref "M1") (pin "4") (pinfunction "PB6_4") (pintype "passive"))
      (node (ref "U2") (pin "120") (pinfunction "PA9/TIM1_CH2/I2C3_SMBA/U1_TX/DCMI_D0/OTG_FS_VBUS_120") (pintype "passive"))
    )
    (net (code "83") (name "/PA10") (class "Default")
      (node (ref "M1") (pin "3") (pinfunction "PB5_3") (pintype "passive"))
      (node (ref "U2") (pin "121") (pinfunction "PA10/TIM1_CH3/U1_RX/OTG_FS_ID/DCMI_D1_121") (pintype "passive"))
    )
    (net (code "84") (name "/PA11") (class "Default")
      (node (ref "P7") (pin "5") (pinfunction "5_5") (pintype "passive"))
      (node (ref "U2") (pin "122") (pinfunction "PA11/TIM1_CH4/U1_CTS/CAN1_RX/LCD_R4/OTG_FS_DM_122") (pintype "passive"))
    )
    (net (code "85") (name "/PB1") (class "Default")
      (node (ref "PWR1") (pin "2") (pinfunction "2_2") (pintype "passive"))
      (node (ref "U2") (pin "57") (pinfunction "PB1/TIM1_CH3N/TIM3_CH4/TIM8_CH3N/LCD_R6/OTG_HS_ULPI_D2/ETH_MII_RXD3/ADC12_IN9_57") (pintype "passive"))
    )
    (net (code "86") (name "/PC12") (class "Default")
      (node (ref "M1") (pin "8") (pinfunction "PA6_8") (pintype "passive"))
      (node (ref "U2") (pin "141") (pinfunction "PC12/SPI3_MOSI/I2S3_SD/U3_CK/U5_TX/SDIO_CK/DCMI_D9_141") (pintype "passive"))
    )
    (net (code "87") (name "/PD2") (class "Default")
      (node (ref "M1") (pin "7") (pinfunction "PA5_7") (pintype "passive"))
      (node (ref "U2") (pin "144") (pinfunction "PD2/TIM3_ETR/U5_RX/SDIO_CMD/DCMI_D11_144") (pintype "passive"))
    )
    (net (code "88") (name "/RESET") (class "Default")
      (node (ref "C6") (pin "2") (pintype "passive"))
      (node (ref "J1") (pin "40") (pinfunction "40_40") (pintype "passive"))
      (node (ref "P1") (pin "5") (pinfunction "5_5") (pintype "passive"))
      (node (ref "R2") (pin "1") (pintype "passive"))
      (node (ref "RST1") (pin "1") (pinfunction "1_1") (pintype "passive"))
      (node (ref "U2") (pin "31") (pinfunction "NRST_31") (pintype "passive"))
    )
    (net (code "89") (name "/SPI5_MISO") (class "Default")
      (node (ref "U2") (pin "26") (pinfunction "PF8/TIM13_CH1/SPI5_MISO/SAI1_SCK_B/FMC_NIOWR/ADC3_IN6_26") (pintype "passive"))
      (node (ref "U3") (pin "2") (pinfunction "SO(IO1)_2") (pintype "passive"))
    )
    (net (code "90") (name "/SPI5_MOSI") (class "Default")
      (node (ref "U2") (pin "27") (pinfunction "PF9/TIM14_CH1/SPI5_MOSI/SAI1_FS_B/FMC_CD/ADC3_IN7_27") (pintype "passive"))
      (node (ref "U3") (pin "5") (pinfunction "SI(IO0)_5") (pintype "power_in"))
    )
    (net (code "91") (name "/SPI5_SCK") (class "Default")
      (node (ref "U2") (pin "25") (pinfunction "PF7/TIM11_CH1/SPI5_SCK/SAI1_MCLK_B/U7_TX/FMC_NREG/ADC3_IN5_25") (pintype "passive"))
      (node (ref "U3") (pin "6") (pinfunction "CLK_6") (pintype "passive"))
    )
    (net (code "92") (name "/T_CS") (class "Default")
      (node (ref "J1") (pin "35") (pinfunction "35_35") (pintype "passive"))
      (node (ref "U2") (pin "7") (pinfunction "PI8/TAMP_2_7") (pintype "passive"))
    )
    (net (code "93") (name "/T_MISO") (class "Default")
      (node (ref "J1") (pin "37") (pinfunction "37_37") (pintype "passive"))
      (node (ref "U2") (pin "107") (pinfunction "PG3/FMC_A13_107") (pintype "passive"))
    )
    (net (code "94") (name "/T_MOSI") (class "Default")
      (node (ref "J1") (pin "36") (pinfunction "36_36") (pintype "passive"))
      (node (ref "U2") (pin "134") (pinfunction "PI3/TIM8_ETR/SPI2_MOSI/I2S2_SD/FMC_D27/DCMI_D10_134") (pintype "passive"))
    )
    (net (code "95") (name "/T_PEN") (class "Default")
      (node (ref "J1") (pin "39") (pinfunction "39_39") (pintype "passive"))
      (node (ref "U2") (pin "84") (pinfunction "PH7/I2C3_SCL/SPI5_MISO/ETH_MII_RXD3/FMC_SDCKE1/DCMI_D9_84") (pintype "passive"))
    )
    (net (code "96") (name "/T_SCK") (class "Default")
      (node (ref "J1") (pin "38") (pinfunction "38_38") (pintype "passive"))
      (node (ref "U2") (pin "83") (pinfunction "PH6/I2C2_SMBA/SPI5_SCK/TIM12_CH1/ETH_MII_RXD2/FMC_SDNE1/DCMI_D8_83") (pintype "passive"))
    )
    (net (code "97") (name "GND") (class "Default")
      (node (ref "BEEP1") (pin "2") (pinfunction "G_2") (pintype "passive"))
      (node (ref "C1") (pin "1") (pintype "passive"))
      (node (ref "C10") (pin "1") (pintype "passive"))
      (node (ref "C11") (pin "2") (pintype "passive"))
      (node (ref "C12") (pin "1") (pintype "passive"))
      (node (ref "C13") (pin "1") (pintype "passive"))
      (node (ref "C14") (pin "2") (pintype "passive"))
      (node (ref "C15") (pin "1") (pintype "passive"))
      (node (ref "C16") (pin "1") (pintype "passive"))
      (node (ref "C17") (pin "2") (pintype "passive"))
      (node (ref "C18") (pin "1") (pintype "passive"))
      (node (ref "C19") (pin "2") (pintype "passive"))
      (node (ref "C2") (pin "1") (pintype "passive"))
      (node (ref "C20") (pin "2") (pintype "passive"))
      (node (ref "C21") (pin "2") (pintype "passive"))
      (node (ref "C22") (pin "2") (pintype "passive"))
      (node (ref "C23") (pin "2") (pintype "passive"))
      (node (ref "C24") (pin "2") (pintype "passive"))
      (node (ref "C25") (pin "2") (pintype "passive"))
      (node (ref "C26") (pin "2") (pintype "passive"))
      (node (ref "C27") (pin "2") (pintype "passive"))
      (node (ref "C28") (pin "2") (pintype "passive"))
      (node (ref "C29") (pin "2") (pintype "passive"))
      (node (ref "C3") (pin "1") (pintype "passive"))
      (node (ref "C30") (pin "2") (pintype "passive"))
      (node (ref "C31") (pin "2") (pintype "passive"))
      (node (ref "C32") (pin "2") (pintype "passive"))
      (node (ref "C33") (pin "2") (pintype "passive"))
      (node (ref "C34") (pin "1") (pintype "passive"))
      (node (ref "C35") (pin "2") (pintype "passive"))
      (node (ref "C37") (pin "1") (pintype "passive"))
      (node (ref "C4") (pin "1") (pintype "passive"))
      (node (ref "C40") (pin "2") (pintype "passive"))
      (node (ref "C41") (pin "2") (pintype "passive"))
      (node (ref "C42") (pin "2") (pintype "passive"))
      (node (ref "C43") (pin "2") (pintype "passive"))
      (node (ref "C44") (pin "1") (pintype "passive"))
      (node (ref "C45") (pin "1") (pintype "passive"))
      (node (ref "C46") (pin "1") (pintype "passive"))
      (node (ref "C47") (pin "1") (pintype "passive"))
      (node (ref "C48") (pin "1") (pintype "passive"))
      (node (ref "C49") (pin "1") (pintype "passive"))
      (node (ref "C5") (pin "1") (pintype "passive"))
      (node (ref "C50") (pin "1") (pintype "passive"))
      (node (ref "C51") (pin "1") (pintype "passive"))
      (node (ref "C52") (pin "1") (pintype "passive"))
      (node (ref "C53") (pin "1") (pintype "passive"))
      (node (ref "C54") (pin "1") (pintype "passive"))
      (node (ref "C55") (pin "1") (pintype "passive"))
      (node (ref "C56") (pin "1") (pintype "passive"))
      (node (ref "C57") (pin "1") (pintype "passive"))
      (node (ref "C6") (pin "1") (pintype "passive"))
      (node (ref "C7") (pin "1") (pintype "passive"))
      (node (ref "C8") (pin "1") (pintype "passive"))
      (node (ref "C9") (pin "1") (pintype "passive"))
      (node (ref "DC_IN1") (pin "2") (pintype "passive"))
      (node (ref "DC_IN1") (pin "3") (pintype "passive"))
      (node (ref "E1") (pin "2") (pinfunction "K_2") (pintype "passive"))
      (node (ref "E2") (pin "2") (pinfunction "K_2") (pintype "passive"))
      (node (ref "GND3") (pin "1") (pinfunction "1_1") (pintype "passive"))
      (node (ref "J1") (pin "11") (pinfunction "11_11") (pintype "passive"))
      (node (ref "J1") (pin "12") (pinfunction "12_12") (pintype "passive"))
      (node (ref "J1") (pin "13") (pinfunction "13_13") (pintype "passive"))
      (node (ref "J1") (pin "20") (pinfunction "20_20") (pintype "passive"))
      (node (ref "J1") (pin "21") (pinfunction "21_21") (pintype "passive"))
      (node (ref "J1") (pin "22") (pinfunction "22_22") (pintype "passive"))
      (node (ref "J1") (pin "23") (pinfunction "23_23") (pintype "passive"))
      (node (ref "J1") (pin "29") (pinfunction "29_29") (pintype "passive"))
      (node (ref "J1") (pin "3") (pinfunction "3_3") (pintype "passive"))
      (node (ref "J1") (pin "4") (pinfunction "4_4") (pintype "passive"))
      (node (ref "J1") (pin "5") (pinfunction "5_5") (pintype "passive"))
      (node (ref "J1") (pin "A") (pinfunction "A_A") (pintype "passive"))
      (node (ref "J1") (pin "B") (pinfunction "B_B") (pintype "passive"))
      (node (ref "M1") (pin "1") (pinfunction "GND_1") (pintype "passive"))
      (node (ref "M1") (pin "10") (pinfunction "GND_10") (pintype "passive"))
      (node (ref "P1") (pin "1") (pinfunction "1_1") (pintype "passive"))
      (node (ref "P3") (pin "1") (pinfunction "1_1") (pintype "passive"))
      (node (ref "P5") (pin "1") (pinfunction "1_1") (pintype "passive"))
      (node (ref "P6") (pin "1") (pinfunction "1_1") (pintype "passive"))
      (node (ref "P7") (pin "10") (pinfunction "10_10") (pintype "passive"))
      (node (ref "P7") (pin "12") (pinfunction "12_12") (pintype "passive"))
      (node (ref "P7") (pin "18") (pinfunction "18_18") (pintype "passive"))
      (node (ref "P7") (pin "8") (pinfunction "8_8") (pintype "passive"))
      (node (ref "R14") (pin "2") (pintype "passive"))
      (node (ref "R19") (pin "1") (pintype "passive"))
      (node (ref "R20") (pin "1") (pintype "passive"))
      (node (ref "R3") (pin "2") (pintype "passive"))
      (node (ref "R4") (pin "2") (pintype "passive"))
      (node (ref "RST1") (pin "2") (pinfunction "2_2") (pintype "passive"))
      (node (ref "U1") (pin "2") (pinfunction "GND_2") (pintype "passive"))
      (node (ref "U2") (pin "102") (pinfunction "VSS_102") (pintype "passive"))
      (node (ref "U2") (pin "113") (pinfunction "VSS_113") (pintype "passive"))
      (node (ref "U2") (pin "126") (pinfunction "VSS_126") (pintype "passive"))
      (node (ref "U2") (pin "135") (pinfunction "VSS_135") (pintype "passive"))
      (node (ref "U2") (pin "14") (pinfunction "VSS_14") (pintype "passive"))
      (node (ref "U2") (pin "148") (pinfunction "VSS_148") (pintype "passive"))
      (node (ref "U2") (pin "158") (pinfunction "VSS_158") (pintype "passive"))
      (node (ref "U2") (pin "22") (pinfunction "VSS_22") (pintype "passive"))
      (node (ref "U2") (pin "37") (pinfunction "VSSA_37") (pintype "passive"))
      (node (ref "U2") (pin "61") (pinfunction "VSS_61") (pintype "passive"))
      (node (ref "U2") (pin "71") (pinfunction "VSS_71") (pintype "passive"))
      (node (ref "U2") (pin "90") (pinfunction "VSS_90") (pintype "passive"))
      (node (ref "U3") (pin "4") (pinfunction "GND_4") (pintype "passive"))
      (node (ref "U4") (pin "12") (pinfunction "VSSQ1_12") (pintype "power_in"))
      (node (ref "U4") (pin "28") (pinfunction "VSS2_28") (pintype "power_in"))
      (node (ref "U4") (pin "41") (pinfunction "VSS0_41") (pintype "power_in"))
      (node (ref "U4") (pin "46") (pinfunction "VSSQ2_46") (pintype "power_in"))
      (node (ref "U4") (pin "52") (pinfunction "VSSQ3_52") (pintype "power_in"))
      (node (ref "U4") (pin "54") (pinfunction "VSS1_54") (pintype "power_in"))
      (node (ref "U4") (pin "6") (pinfunction "VSSQ0_6") (pintype "power_in"))
      (node (ref "U5") (pin "4") (pinfunction "GND_4") (pintype "passive"))
      (node (ref "U6") (pin "1") (pinfunction "GND_1") (pintype "passive"))
      (node (ref "U7") (pin "1") (pinfunction "GND_1") (pintype "passive"))
      (node (ref "U8") (pin "1") (pinfunction "GND_1") (pintype "passive"))
      (node (ref "U9") (pin "10") (pinfunction "GND_10") (pintype "passive"))
      (node (ref "U9") (pin "6") (pinfunction "GND_6") (pintype "passive"))
      (node (ref "Y2") (pin "2") (pinfunction "GND_2") (pintype "passive"))
      (node (ref "Y2") (pin "4") (pinfunction "GND_4") (pintype "passive"))
    )
    (net (code "98") (name "Net-(BEEP1-P)") (class "Default")
      (node (ref "BEEP1") (pin "1") (pinfunction "P_1") (pintype "passive"))
      (node (ref "Q1") (pin "3") (pinfunction "C_3") (pintype "passive"))
    )
    (net (code "99") (name "Net-(C39-Pad2)") (class "Default")
      (node (ref "C39") (pin "2") (pintype "passive"))
      (node (ref "R12") (pin "1") (pintype "passive"))
    )
    (net (code "100") (name "Net-(D1-Pad1)") (class "Default")
      (node (ref "D1") (pin "1") (pintype "passive"))
      (node (ref "DC_IN1") (pin "1") (pintype "passive"))
    )
    (net (code "101") (name "Net-(M1-PA0)") (class "Default")
      (node (ref "M1") (pin "12") (pinfunction "PA0_12") (pintype "passive"))
      (node (ref "U5") (pin "2") (pinfunction "DQ_2") (pintype "passive"))
    )
    (net (code "102") (name "Net-(M1-SPK+)") (class "Default")
      (node (ref "M1") (pin "16") (pinfunction "SPK+_16") (pintype "passive"))
      (node (ref "P2") (pin "1") (pinfunction "1_1") (pintype "passive"))
    )
    (net (code "103") (name "Net-(M1-SPK-)") (class "Default")
      (node (ref "M1") (pin "15") (pinfunction "SPK-_15") (pintype "passive"))
      (node (ref "P2") (pin "2") (pinfunction "2_2") (pintype "passive"))
    )
    (net (code "104") (name "Net-(P4-Pad1)") (class "Default")
      (node (ref "P4") (pin "1") (pinfunction "1_1") (pintype "passive"))
      (node (ref "R16") (pin "2") (pintype "passive"))
    )
    (net (code "105") (name "Net-(P4-Pad2)") (class "Default")
      (node (ref "P4") (pin "2") (pinfunction "2_2") (pintype "passive"))
      (node (ref "R15") (pin "2") (pintype "passive"))
    )
    (net (code "106") (name "Net-(PWR1-Pad1)") (class "Default")
      (node (ref "PWR1") (pin "1") (pinfunction "1_1") (pintype "passive"))
      (node (ref "R1") (pin "2") (pintype "passive"))
    )
    (net (code "107") (name "Net-(Q1-B)") (class "Default")
      (node (ref "Q1") (pin "1") (pinfunction "B_1") (pintype "passive"))
      (node (ref "R10") (pin "2") (pintype "passive"))
    )
    (net (code "108") (name "Net-(Q2-G)") (class "Default")
      (node (ref "Q2") (pin "1") (pinfunction "G_1") (pintype "passive"))
      (node (ref "R17") (pin "2") (pintype "passive"))
      (node (ref "R19") (pin "2") (pintype "passive"))
    )
    (net (code "109") (name "Net-(Q2-S)") (class "Default")
      (node (ref "P5") (pin "2") (pinfunction "2_2") (pintype "passive"))
      (node (ref "Q2") (pin "3") (pinfunction "S_3") (pintype "passive"))
    )
    (net (code "110") (name "Net-(Q3-G)") (class "Default")
      (node (ref "Q3") (pin "1") (pinfunction "G_1") (pintype "passive"))
      (node (ref "R18") (pin "2") (pintype "passive"))
      (node (ref "R20") (pin "2") (pintype "passive"))
    )
    (net (code "111") (name "Net-(Q3-S)") (class "Default")
      (node (ref "P6") (pin "2") (pinfunction "2_2") (pintype "passive"))
      (node (ref "Q3") (pin "3") (pinfunction "S_3") (pintype "passive"))
    )
    (net (code "112") (name "Net-(U1-BYP)") (class "Default")
      (node (ref "C2") (pin "2") (pintype "passive"))
      (node (ref "U1") (pin "4") (pinfunction "BYP_4") (pintype "passive"))
    )
    (net (code "113") (name "Net-(U2-BYPASS_REG)") (class "Default")
      (node (ref "R4") (pin "1") (pintype "passive"))
      (node (ref "U2") (pin "48") (pinfunction "BYPASS_REG_48") (pintype "passive"))
    )
    (net (code "114") (name "Net-(U2-PC14{slash}OSC32_IN)") (class "Default")
      (node (ref "C15") (pin "2") (pintype "passive"))
      (node (ref "U2") (pin "9") (pinfunction "PC14/OSC32_IN_9") (pintype "passive"))
      (node (ref "Y1") (pin "1") (pinfunction "OSC1_1") (pintype "passive"))
    )
    (net (code "115") (name "Net-(U2-PC15{slash}OSC32_OUT)") (class "Default")
      (node (ref "C16") (pin "2") (pintype "passive"))
      (node (ref "U2") (pin "10") (pinfunction "PC15/OSC32_OUT_10") (pintype "passive"))
      (node (ref "Y1") (pin "2") (pinfunction "OSC2_2") (pintype "passive"))
    )
    (net (code "116") (name "Net-(U2-PDR_ON)") (class "Default")
      (node (ref "R7") (pin "1") (pintype "passive"))
      (node (ref "U2") (pin "171") (pinfunction "PDR_ON_171") (pintype "passive"))
    )
    (net (code "117") (name "Net-(U2-PH0{slash}OSC_IN)") (class "Default")
      (node (ref "C14") (pin "1") (pintype "passive"))
      (node (ref "U2") (pin "29") (pinfunction "PH0/OSC_IN_29") (pintype "passive"))
      (node (ref "Y2") (pin "3") (pinfunction "HOT_3") (pintype "passive"))
    )
    (net (code "118") (name "Net-(U2-PH1{slash}OSC_OUT)") (class "Default")
      (node (ref "C17") (pin "1") (pintype "passive"))
      (node (ref "U2") (pin "30") (pinfunction "PH1/OSC_OUT_30") (pintype "passive"))
      (node (ref "Y2") (pin "1") (pinfunction "HOT_1") (pintype "passive"))
    )
    (net (code "119") (name "Net-(U2-VCAP_1)") (class "Default")
      (node (ref "C8") (pin "2") (pintype "passive"))
      (node (ref "U2") (pin "81") (pinfunction "VCAP_1_81") (pintype "passive"))
    )
    (net (code "120") (name "Net-(U2-VCAP_2)") (class "Default")
      (node (ref "C9") (pin "2") (pintype "passive"))
      (node (ref "U2") (pin "125") (pinfunction "VCAP_2_125") (pintype "passive"))
    )
    (net (code "121") (name "Net-(U2-VREF+)") (class "Default")
      (node (ref "C10") (pin "2") (pintype "passive"))
      (node (ref "C11") (pin "1") (pintype "passive"))
      (node (ref "R5") (pin "1") (pintype "passive"))
      (node (ref "U2") (pin "38") (pinfunction "VREF+_38") (pintype "passive"))
    )
    (net (code "122") (name "Net-(U6-BST)") (class "Default")
      (node (ref "C38") (pin "2") (pintype "passive"))
      (node (ref "U6") (pin "6") (pinfunction "BST_6") (pintype "passive"))
    )
    (net (code "123") (name "Net-(U6-EN)") (class "Default")
      (node (ref "R11") (pin "2") (pintype "passive"))
      (node (ref "U6") (pin "5") (pinfunction "EN_5") (pintype "passive"))
    )
    (net (code "124") (name "Net-(U6-FB)") (class "Default")
      (node (ref "R12") (pin "2") (pintype "passive"))
      (node (ref "R13") (pin "2") (pintype "passive"))
      (node (ref "R14") (pin "1") (pintype "passive"))
      (node (ref "U6") (pin "4") (pinfunction "FB_4") (pintype "passive"))
    )
    (net (code "125") (name "Net-(U6-SW)") (class "Default")
      (node (ref "C38") (pin "1") (pintype "passive"))
      (node (ref "L1") (pin "1") (pinfunction "1_1") (pintype "passive"))
      (node (ref "U6") (pin "2") (pinfunction "SW_2") (pintype "passive"))
    )
    (net (code "126") (name "Net-(U6-VIN)") (class "Default")
      (node (ref "C41") (pin "1") (pintype "passive"))
      (node (ref "C42") (pin "1") (pintype "passive"))
      (node (ref "D1") (pin "2") (pintype "passive"))
      (node (ref "R11") (pin "1") (pintype "passive"))
      (node (ref "U6") (pin "3") (pinfunction "VIN_3") (pintype "passive"))
    )
    (net (code "127") (name "Net-(U9-I2C_SCL)") (class "Default")
      (node (ref "R25") (pin "1") (pintype "passive"))
      (node (ref "U9") (pin "3") (pinfunction "I2C_SCL_3") (pintype "passive"))
    )
    (net (code "128") (name "Net-(U9-I2C_SDA)") (class "Default")
      (node (ref "R23") (pin "1") (pintype "passive"))
      (node (ref "U9") (pin "2") (pinfunction "I2C_SDA_2") (pintype "passive"))
    )
    (net (code "129") (name "Net-(U9-INT)") (class "Default")
      (node (ref "R27") (pin "1") (pintype "passive"))
      (node (ref "U9") (pin "4") (pinfunction "INT_4") (pintype "passive"))
    )
    (net (code "130") (name "VBTN") (class "Default")
      (node (ref "C39") (pin "1") (pintype "passive"))
      (node (ref "C40") (pin "1") (pintype "passive"))
      (node (ref "E1") (pin "1") (pinfunction "A_1") (pintype "passive"))
      (node (ref "K1") (pin "3") (pinfunction "I/O1_3") (pintype "passive"))
      (node (ref "L1") (pin "2") (pinfunction "2_2") (pintype "passive"))
      (node (ref "R13") (pin "1") (pintype "passive"))
    )
    (net (code "131") (name "VCC3.3") (class "Default")
      (node (ref "C18") (pin "2") (pintype "passive"))
      (node (ref "C3") (pin "2") (pintype "passive"))
      (node (ref "C4") (pin "2") (pintype "passive"))
      (node (ref "C51") (pin "2") (pintype "passive"))
      (node (ref "C52") (pin "2") (pintype "passive"))
      (node (ref "C53") (pin "2") (pintype "passive"))
      (node (ref "C54") (pin "2") (pintype "passive"))
      (node (ref "C55") (pin "2") (pintype "passive"))
      (node (ref "C56") (pin "2") (pintype "passive"))
      (node (ref "C57") (pin "2") (pintype "passive"))
      (node (ref "GND2") (pin "1") (pinfunction "1_1") (pintype "passive"))
      (node (ref "P1") (pin "4") (pinfunction "4_4") (pintype "passive"))
      (node (ref "P7") (pin "2") (pinfunction "2_2") (pintype "passive"))
      (node (ref "P7") (pin "4") (pinfunction "4_4") (pintype "passive"))
      (node (ref "P7") (pin "6") (pinfunction "6_6") (pintype "passive"))
      (node (ref "Q1") (pin "2") (pinfunction "E_2") (pintype "passive"))
      (node (ref "R1") (pin "1") (pintype "passive"))
      (node (ref "R2") (pin "2") (pintype "passive"))
      (node (ref "R21") (pin "2") (pintype "passive"))
      (node (ref "R8") (pin "1") (pintype "passive"))
      (node (ref "R9") (pin "1") (pintype "passive"))
      (node (ref "U1") (pin "5") (pinfunction "OUT_5") (pintype "passive"))
      (node (ref "U3") (pin "3") (pinfunction "~{WP}(IO2)_3") (pintype "passive"))
      (node (ref "U3") (pin "7") (pinfunction "HOLD/RST(IO3)_7") (pintype "power_in"))
      (node (ref "U3") (pin "8") (pinfunction "VCC_8") (pintype "passive"))
      (node (ref "U4") (pin "1") (pinfunction "VDD0_1") (pintype "power_in"))
      (node (ref "U4") (pin "14") (pinfunction "VDD1_14") (pintype "power_in"))
      (node (ref "U4") (pin "27") (pinfunction "VDD2_27") (pintype "power_in"))
      (node (ref "U4") (pin "3") (pinfunction "VDDQ0_3") (pintype "power_in"))
      (node (ref "U4") (pin "43") (pinfunction "VDDQ2_43") (pintype "power_in"))
      (node (ref "U4") (pin "49") (pinfunction "VDDQ3_49") (pintype "power_in"))
      (node (ref "U4") (pin "9") (pinfunction "VDDQ1_9") (pintype "power_in"))
    )
    (net (code "132") (name "VCC3.3M") (class "Default")
      (node (ref "C19") (pin "1") (pintype "passive"))
      (node (ref "C20") (pin "1") (pintype "passive"))
      (node (ref "C21") (pin "1") (pintype "passive"))
      (node (ref "C22") (pin "1") (pintype "passive"))
      (node (ref "C23") (pin "1") (pintype "passive"))
      (node (ref "C24") (pin "1") (pintype "passive"))
      (node (ref "C25") (pin "1") (pintype "passive"))
      (node (ref "C26") (pin "1") (pintype "passive"))
      (node (ref "C27") (pin "1") (pintype "passive"))
      (node (ref "C28") (pin "1") (pintype "passive"))
      (node (ref "C29") (pin "1") (pintype "passive"))
      (node (ref "C30") (pin "1") (pintype "passive"))
      (node (ref "C31") (pin "1") (pintype "passive"))
      (node (ref "C32") (pin "1") (pintype "passive"))
      (node (ref "C33") (pin "1") (pintype "passive"))
      (node (ref "C7") (pin "2") (pintype "passive"))
      (node (ref "R6") (pin "2") (pintype "passive"))
      (node (ref "R7") (pin "2") (pintype "passive"))
      (node (ref "R8") (pin "2") (pintype "passive"))
      (node (ref "R9") (pin "2") (pintype "passive"))
      (node (ref "U2") (pin "103") (pinfunction "VDD_103") (pintype "passive"))
      (node (ref "U2") (pin "114") (pinfunction "VDD_114") (pintype "passive"))
      (node (ref "U2") (pin "127") (pinfunction "VDD_127") (pintype "passive"))
      (node (ref "U2") (pin "136") (pinfunction "VDD_136") (pintype "passive"))
      (node (ref "U2") (pin "149") (pinfunction "VDD_149") (pintype "passive"))
      (node (ref "U2") (pin "15") (pinfunction "VDD_15") (pintype "passive"))
      (node (ref "U2") (pin "159") (pinfunction "VDD_159") (pintype "passive"))
      (node (ref "U2") (pin "172") (pinfunction "VDD_172") (pintype "passive"))
      (node (ref "U2") (pin "23") (pinfunction "VDD_23") (pintype "passive"))
      (node (ref "U2") (pin "36") (pinfunction "VDD_36") (pintype "passive"))
      (node (ref "U2") (pin "49") (pinfunction "VDD_49") (pintype "passive"))
      (node (ref "U2") (pin "6") (pinfunction "VBAT_6") (pintype "passive"))
      (node (ref "U2") (pin "62") (pinfunction "VDD_62") (pintype "passive"))
      (node (ref "U2") (pin "72") (pinfunction "VDD_72") (pintype "passive"))
      (node (ref "U2") (pin "82") (pinfunction "VDD_82") (pintype "passive"))
      (node (ref "U2") (pin "91") (pinfunction "VDD_91") (pintype "passive"))
    )
    (net (code "133") (name "VCC5") (class "Default")
      (node (ref "C1") (pin "2") (pintype "passive"))
      (node (ref "C35") (pin "1") (pintype "passive"))
      (node (ref "C37") (pin "2") (pintype "passive"))
      (node (ref "C43") (pin "1") (pintype "passive"))
      (node (ref "C45") (pin "2") (pintype "passive"))
      (node (ref "C48") (pin "2") (pintype "passive"))
      (node (ref "C5") (pin "2") (pintype "passive"))
      (node (ref "E2") (pin "1") (pinfunction "A_1") (pintype "passive"))
      (node (ref "GND1") (pin "1") (pinfunction "1_1") (pintype "passive"))
      (node (ref "J1") (pin "1") (pinfunction "1_1") (pintype "passive"))
      (node (ref "J1") (pin "2") (pinfunction "2_2") (pintype "passive"))
      (node (ref "K1") (pin "2") (pinfunction "TAP1_2") (pintype "passive"))
      (node (ref "M1") (pin "2") (pinfunction "5V_2") (pintype "passive"))
      (node (ref "P3") (pin "2") (pinfunction "2_2") (pintype "passive"))
      (node (ref "P7") (pin "14") (pinfunction "14_14") (pintype "passive"))
      (node (ref "P7") (pin "16") (pinfunction "16_16") (pintype "passive"))
      (node (ref "Q2") (pin "2") (pinfunction "D_2") (pintype "passive"))
      (node (ref "Q3") (pin "2") (pinfunction "D_2") (pintype "passive"))
      (node (ref "U1") (pin "1") (pinfunction "VIN_1") (pintype "passive"))
      (node (ref "U1") (pin "3") (pinfunction "CE_3") (pintype "passive"))
      (node (ref "U5") (pin "1") (pinfunction "VCC_1") (pintype "passive"))
      (node (ref "U7") (pin "3") (pinfunction "VIN_3") (pintype "passive"))
      (node (ref "U8") (pin "3") (pinfunction "VIN_3") (pintype "passive"))
    )
    (net (code "134") (name "VDD") (class "Default")
      (node (ref "C46") (pin "2") (pintype "passive"))
      (node (ref "C47") (pin "2") (pintype "passive"))
      (node (ref "C50") (pin "2") (pintype "passive"))
      (node (ref "R22") (pin "2") (pintype "passive"))
      (node (ref "R24") (pin "2") (pintype "passive"))
      (node (ref "R26") (pin "2") (pintype "passive"))
      (node (ref "U8") (pin "2") (pinfunction "VOUT_2") (pintype "passive"))
      (node (ref "U9") (pin "1") (pinfunction "VBUS_1") (pintype "passive"))
      (node (ref "U9") (pin "12") (pinfunction "VDD(Vmain)_12") (pintype "passive"))
    )
    (net (code "135") (name "VDDA") (class "Default")
      (node (ref "C12") (pin "2") (pintype "passive"))
      (node (ref "C13") (pin "2") (pintype "passive"))
      (node (ref "R5") (pin "2") (pintype "passive"))
      (node (ref "R6") (pin "1") (pintype "passive"))
      (node (ref "U2") (pin "39") (pinfunction "VDDA_39") (pintype "passive"))
    )
    (net (code "136") (name "VLED") (class "Default")
      (node (ref "C34") (pin "2") (pintype "passive"))
      (node (ref "C44") (pin "2") (pintype "passive"))
      (node (ref "C49") (pin "2") (pintype "passive"))
      (node (ref "U7") (pin "2") (pinfunction "VOUT_2") (pintype "passive"))
      (node (ref "U9") (pin "11") (pinfunction "VLED_11") (pintype "passive"))
    )
    (net (code "137") (name "unconnected-(K1-I{slash}O1-Pad1)") (class "Default")
      (node (ref "K1") (pin "1") (pinfunction "I/O1_1") (pintype "passive"))
    )
    (net (code "138") (name "unconnected-(K1-I{slash}O2-Pad4)") (class "Default")
      (node (ref "K1") (pin "4") (pinfunction "I/O2_4") (pintype "passive"))
    )
    (net (code "139") (name "unconnected-(K1-I{slash}O2-Pad6)") (class "Default")
      (node (ref "K1") (pin "6") (pinfunction "I/O2_6") (pintype "passive"))
    )
    (net (code "140") (name "unconnected-(K1-TAP2-Pad5)") (class "Default")
      (node (ref "K1") (pin "5") (pinfunction "TAP2_5") (pintype "passive"))
    )
    (net (code "141") (name "unconnected-(M1-3V3-Pad11)") (class "Default")
      (node (ref "M1") (pin "11") (pinfunction "3V3_11") (pintype "passive"))
    )
    (net (code "142") (name "unconnected-(M1-PA1-Pad13)") (class "Default")
      (node (ref "M1") (pin "13") (pinfunction "PA1_13") (pintype "passive"))
    )
    (net (code "143") (name "unconnected-(M1-PA4-Pad9)") (class "Default")
      (node (ref "M1") (pin "9") (pinfunction "PA4_9") (pintype "passive"))
    )
    (net (code "144") (name "unconnected-(M1-PC4-Pad14)") (class "Default")
      (node (ref "M1") (pin "14") (pinfunction "PC4_14") (pintype "passive"))
    )
    (net (code "145") (name "unconnected-(P7-Pad7)") (class "Default")
      (node (ref "P7") (pin "7") (pinfunction "7_7") (pintype "passive"))
    )
    (net (code "146") (name "unconnected-(U2-PA12{slash}TIM1_ETR{slash}U1_RTS{slash}CAN1_TX{slash}LCD_R5{slash}OTG_FS_DP-Pad123)") (class "Default")
      (node (ref "U2") (pin "123") (pinfunction "PA12/TIM1_ETR/U1_RTS/CAN1_TX/LCD_R5/OTG_FS_DP_123") (pintype "passive"))
    )
    (net (code "147") (name "unconnected-(U2-PA15{slash}JTDI{slash}TIM2_CH1{slash}TIM2_ETR{slash}SPI1_NSS{slash}SPI3_NSS{slash}I2S3_WS-Pad138)") (class "Default")
      (node (ref "U2") (pin "138") (pinfunction "PA15/JTDI/TIM2_CH1/TIM2_ETR/SPI1_NSS/SPI3_NSS/I2S3_WS_138") (pintype "passive"))
    )
    (net (code "148") (name "unconnected-(U2-PB0{slash}TIM1_CH2N{slash}TIM3_CH3{slash}TIM8_CH2N{slash}LCD_R3{slash}OTG_HS_ULPI_D1{slash}ETH_MII_RXD2{slash}ADC12_IN8-Pad56)") (class "Default")
      (node (ref "U2") (pin "56") (pinfunction "PB0/TIM1_CH2N/TIM3_CH3/TIM8_CH2N/LCD_R3/OTG_HS_ULPI_D1/ETH_MII_RXD2/ADC12_IN8_56") (pintype "passive"))
    )
    (net (code "149") (name "unconnected-(U2-PB2{slash}BOOT1-Pad58)") (class "Default")
      (node (ref "U2") (pin "58") (pinfunction "PB2/BOOT1_58") (pintype "passive"))
    )
    (net (code "150") (name "unconnected-(U2-PB3{slash}JTDO{slash}TIM2_CH2{slash}SPI1_SCK{slash}SPI3_SCK{slash}I2S3_CK-Pad161)") (class "Default")
      (node (ref "U2") (pin "161") (pinfunction "PB3/JTDO/TIM2_CH2/SPI1_SCK/SPI3_SCK/I2S3_CK_161") (pintype "passive"))
    )
    (net (code "151") (name "unconnected-(U2-PB4{slash}NJTRST{slash}TIM3_CH1{slash}SPI1_MISO{slash}SPI3_MISO{slash}I2S3ext_SD-Pad162)") (class "Default")
      (node (ref "U2") (pin "162") (pinfunction "PB4/NJTRST/TIM3_CH1/SPI1_MISO/SPI3_MISO/I2S3ext_SD_162") (pintype "passive"))
    )
    (net (code "152") (name "unconnected-(U2-PB6{slash}TIM4_CH1{slash}I2C1_SCL{slash}U1_TX{slash}CAN2_TX{slash}FMC_SDNE1{slash}DCMI_D5-Pad164)") (class "Default")
      (node (ref "U2") (pin "164") (pinfunction "PB6/TIM4_CH1/I2C1_SCL/U1_TX/CAN2_TX/FMC_SDNE1/DCMI_D5_164") (pintype "passive"))
    )
    (net (code "153") (name "unconnected-(U2-PB7{slash}TIM4_CH2{slash}I2C1_SDA{slash}U1_RX{slash}FMC_NL{slash}DCMI_VSYNC-Pad165)") (class "Default")
      (node (ref "U2") (pin "165") (pinfunction "PB7/TIM4_CH2/I2C1_SDA/U1_RX/FMC_NL/DCMI_VSYNC_165") (pintype "passive"))
    )
    (net (code "154") (name "unconnected-(U2-PB8{slash}TIM4_CH3{slash}TIM10_CH1{slash}I2C1_SCL{slash}CAN1_RX{slash}ETH_MII_TXD3{slash}SDIO_D4{slash}DCMI_D6{slash}LCD_B6-Pad167)") (class "Default")
      (node (ref "U2") (pin "167") (pinfunction "PB8/TIM4_CH3/TIM10_CH1/I2C1_SCL/CAN1_RX/ETH_MII_TXD3/SDIO_D4/DCMI_D6/LCD_B6_167") (pintype "passive"))
    )
    (net (code "155") (name "unconnected-(U2-PB12{slash}TIM1_BKIN{slash}I2C2_SMBA{slash}SPI2_NSS{slash}I2S2_WS{slash}U3_CK{slash}CAN2_RX{slash}OTG_HS_ULPI_D5{slash}ETH_MII_TXD0{slash}ETH_RMII_TXD0{slash}OTG_HS_ID-Pad92)") (class "Default")
      (node (ref "U2") (pin "92") (pinfunction "PB12/TIM1_BKIN/I2C2_SMBA/SPI2_NSS/I2S2_WS/U3_CK/CAN2_RX/OTG_HS_ULPI_D5/ETH_MII_TXD0/ETH_RMII_TXD0/OTG_HS_ID_92") (pintype "passive"))
    )
    (net (code "156") (name "unconnected-(U2-PB13{slash}TIM1_CH1N{slash}SPI2_SCK{slash}I2S2_CK{slash}U3_CTS{slash}CAN2_TX{slash}OTG_HS_ULPI_D6{slash}ETH_MII_TXD1{slash}ETH_RMII_TXD1{slash}OTG_HS_VBUS-Pad93)") (class "Default")
      (node (ref "U2") (pin "93") (pinfunction "PB13/TIM1_CH1N/SPI2_SCK/I2S2_CK/U3_CTS/CAN2_TX/OTG_HS_ULPI_D6/ETH_MII_TXD1/ETH_RMII_TXD1/OTG_HS_VBUS_93") (pintype "passive"))
    )
    (net (code "157") (name "unconnected-(U2-PB14{slash}TIM1_CH2N{slash}TIM8_CH2N{slash}SPI2_MISO{slash}I2S2ext_SD{slash}U3_RTS{slash}TIM12_CH1{slash}OTG_HS_DM-Pad94)") (class "Default")
      (node (ref "U2") (pin "94") (pinfunction "PB14/TIM1_CH2N/TIM8_CH2N/SPI2_MISO/I2S2ext_SD/U3_RTS/TIM12_CH1/OTG_HS_DM_94") (pintype "passive"))
    )
    (net (code "158") (name "unconnected-(U2-PC1{slash}ETH_MDC{slash}ADC123_IN11-Pad33)") (class "Default")
      (node (ref "U2") (pin "33") (pinfunction "PC1/ETH_MDC/ADC123_IN11_33") (pintype "passive"))
    )
    (net (code "159") (name "unconnected-(U2-PC4{slash}ETH_MII_RXD0{slash}ETH_RMII_RXD0{slash}ADC12_IN14-Pad54)") (class "Default")
      (node (ref "U2") (pin "54") (pinfunction "PC4/ETH_MII_RXD0/ETH_RMII_RXD0/ADC12_IN14_54") (pintype "passive"))
    )
    (net (code "160") (name "unconnected-(U2-PC5{slash}ETH_MII_RXD1{slash}ETH_RMII_RXD1{slash}ADC12_IN15-Pad55)") (class "Default")
      (node (ref "U2") (pin "55") (pinfunction "PC5/ETH_MII_RXD1/ETH_RMII_RXD1/ADC12_IN15_55") (pintype "passive"))
    )
    (net (code "161") (name "unconnected-(U2-PC8{slash}TIM3_CH3{slash}TIM8_CH3{slash}U6_CK{slash}SDIO_D0{slash}DCMI_D2-Pad117)") (class "Default")
      (node (ref "U2") (pin "117") (pinfunction "PC8/TIM3_CH3/TIM8_CH3/U6_CK/SDIO_D0/DCMI_D2_117") (pintype "passive"))
    )
    (net (code "162") (name "unconnected-(U2-PC9{slash}MCO2{slash}TIM3_CH4{slash}TIM8_CH4{slash}I2C3_SDA{slash}I2S_CKIN{slash}SDIO_D1{slash}DCMI_D3-Pad118)") (class "Default")
      (node (ref "U2") (pin "118") (pinfunction "PC9/MCO2/TIM3_CH4/TIM8_CH4/I2C3_SDA/I2S_CKIN/SDIO_D1/DCMI_D3_118") (pintype "passive"))
    )
    (net (code "163") (name "unconnected-(U2-PC10{slash}SPI3_SCK{slash}I2S3_CK{slash}U3_TX{slash}U4_TX{slash}SDIO_D2{slash}DCMI_D8{slash}LCD_R2-Pad139)") (class "Default")
      (node (ref "U2") (pin "139") (pinfunction "PC10/SPI3_SCK/I2S3_CK/U3_TX/U4_TX/SDIO_D2/DCMI_D8/LCD_R2_139") (pintype "passive"))
    )
    (net (code "164") (name "unconnected-(U2-PC11{slash}I2S3ext_SD{slash}SPI3_MISO{slash}U3_RX{slash}U4_RX{slash}SDIO_D3{slash}DCMI_D4-Pad140)") (class "Default")
      (node (ref "U2") (pin "140") (pinfunction "PC11/I2S3ext_SD/SPI3_MISO/U3_RX/U4_RX/SDIO_D3/DCMI_D4_140") (pintype "passive"))
    )
    (net (code "165") (name "unconnected-(U2-PC13{slash}TAMP_1-Pad8)") (class "Default")
      (node (ref "U2") (pin "8") (pinfunction "PC13/TAMP_1_8") (pintype "passive"))
    )
    (net (code "166") (name "unconnected-(U2-PD3{slash}SPI2_SCK{slash}I2S2_CK{slash}U2_CTS{slash}FMC_CLK{slash}DCMI_D5{slash}LCD_G7-Pad145)") (class "Default")
      (node (ref "U2") (pin "145") (pinfunction "PD3/SPI2_SCK/I2S2_CK/U2_CTS/FMC_CLK/DCMI_D5/LCD_G7_145") (pintype "passive"))
    )
    (net (code "167") (name "unconnected-(U2-PD4{slash}U2_RTS{slash}FMC_NOE-Pad146)") (class "Default")
      (node (ref "U2") (pin "146") (pinfunction "PD4/U2_RTS/FMC_NOE_146") (pintype "passive"))
    )
    (net (code "168") (name "unconnected-(U2-PD5{slash}U2_TX{slash}FMC_NWE-Pad147)") (class "Default")
      (node (ref "U2") (pin "147") (pinfunction "PD5/U2_TX/FMC_NWE_147") (pintype "passive"))
    )
    (net (code "169") (name "unconnected-(U2-PD6{slash}SPI3_MOSI{slash}I2S3_SD{slash}SAI1_SD_A{slash}U2_RX{slash}FMC_NWAIT{slash}DCMI_D10{slash}LCD_B2-Pad150)") (class "Default")
      (node (ref "U2") (pin "150") (pinfunction "PD6/SPI3_MOSI/I2S3_SD/SAI1_SD_A/U2_RX/FMC_NWAIT/DCMI_D10/LCD_B2_150") (pintype "passive"))
    )
    (net (code "170") (name "unconnected-(U2-PD7{slash}U2_CK{slash}FMC_NE1{slash}FMC_NCE2-Pad151)") (class "Default")
      (node (ref "U2") (pin "151") (pinfunction "PD7/U2_CK/FMC_NE1/FMC_NCE2_151") (pintype "passive"))
    )
    (net (code "171") (name "unconnected-(U2-PD11{slash}U3_CTS{slash}FMC_A16-Pad99)") (class "Default")
      (node (ref "U2") (pin "99") (pinfunction "PD11/U3_CTS/FMC_A16_99") (pintype "passive"))
    )
    (net (code "172") (name "unconnected-(U2-PD12{slash}TIM4_CH1{slash}U3_RTS{slash}FMC_A17-Pad100)") (class "Default")
      (node (ref "U2") (pin "100") (pinfunction "PD12/TIM4_CH1/U3_RTS/FMC_A17_100") (pintype "passive"))
    )
    (net (code "173") (name "unconnected-(U2-PD13{slash}TIM4_CH2{slash}FMC_A18-Pad101)") (class "Default")
      (node (ref "U2") (pin "101") (pinfunction "PD13/TIM4_CH2/FMC_A18_101") (pintype "passive"))
    )
    (net (code "174") (name "unconnected-(U2-PE2{slash}SPI4_SCK{slash}SAI1_MCLK_A{slash}ETH_MII_TXD3{slash}FMC_A23-Pad1)") (class "Default")
      (node (ref "U2") (pin "1") (pinfunction "PE2/SPI4_SCK/SAI1_MCLK_A/ETH_MII_TXD3/FMC_A23_1") (pintype "passive"))
    )
    (net (code "175") (name "unconnected-(U2-PE3{slash}SAI1_SD_B{slash}FMC_A19-Pad2)") (class "Default")
      (node (ref "U2") (pin "2") (pinfunction "PE3/SAI1_SD_B/FMC_A19_2") (pintype "passive"))
    )
    (net (code "176") (name "unconnected-(U2-PE4{slash}SPI4_NSS{slash}SAI1_FS_A{slash}FMC_A20{slash}DCMI_D4{slash}LCD_B0-Pad3)") (class "Default")
      (node (ref "U2") (pin "3") (pinfunction "PE4/SPI4_NSS/SAI1_FS_A/FMC_A20/DCMI_D4/LCD_B0_3") (pintype "passive"))
    )
    (net (code "177") (name "unconnected-(U2-PG9{slash}U6_RX{slash}FMC_NE2{slash}FMC_NCE3-Pad152)") (class "Default")
      (node (ref "U2") (pin "152") (pinfunction "PG9/U6_RX/FMC_NE2/FMC_NCE3_152") (pintype "passive"))
    )
    (net (code "178") (name "unconnected-(U2-PG10{slash}LCD_G3{slash}FMC_NE3{slash}FMC_NCE4_1{slash}DCMI_D2{slash}LCD_B2-Pad153)") (class "Default")
      (node (ref "U2") (pin "153") (pinfunction "PG10/LCD_G3/FMC_NE3/FMC_NCE4_1/DCMI_D2/LCD_B2_153") (pintype "passive"))
    )
    (net (code "179") (name "unconnected-(U2-PG12{slash}SPI6_MISO{slash}U6_RTS{slash}FMC_NE4{slash}LCD_B1{slash}LCD_B4-Pad155)") (class "Default")
      (node (ref "U2") (pin "155") (pinfunction "PG12/SPI6_MISO/U6_RTS/FMC_NE4/LCD_B1/LCD_B4_155") (pintype "passive"))
    )
    (net (code "180") (name "unconnected-(U2-PG13{slash}SPI6_SCK{slash}U6_CTS{slash}ETH_MII_TXD0{slash}ETH_RMII_TXD0{slash}FMC_A24-Pad156)") (class "Default")
      (node (ref "U2") (pin "156") (pinfunction "PG13/SPI6_SCK/U6_CTS/ETH_MII_TXD0/ETH_RMII_TXD0/FMC_A24_156") (pintype "passive"))
    )
    (net (code "181") (name "unconnected-(U2-PG14{slash}SPI6_MOSI{slash}U6_TX{slash}ETH_MII_TXD1{slash}ETH_RMII_TXD1{slash}FMC_A25-Pad157)") (class "Default")
      (node (ref "U2") (pin "157") (pinfunction "PG14/SPI6_MOSI/U6_TX/ETH_MII_TXD1/ETH_RMII_TXD1/FMC_A25_157") (pintype "passive"))
    )
    (net (code "182") (name "unconnected-(U2-PH2{slash}ETH_MII_CRS{slash}FMC_SDCKE0{slash}LCD_R0-Pad43)") (class "Default")
      (node (ref "U2") (pin "43") (pinfunction "PH2/ETH_MII_CRS/FMC_SDCKE0/LCD_R0_43") (pintype "passive"))
    )
    (net (code "183") (name "unconnected-(U2-PH3{slash}ETH_MII_COL{slash}FMC_SDNE0{slash}LCD_R1-Pad44)") (class "Default")
      (node (ref "U2") (pin "44") (pinfunction "PH3/ETH_MII_COL/FMC_SDNE0/LCD_R1_44") (pintype "passive"))
    )
    (net (code "184") (name "unconnected-(U2-PH4{slash}I2C2_SCL{slash}OTG_HS_ULPI_NXT-Pad45)") (class "Default")
      (node (ref "U2") (pin "45") (pinfunction "PH4/I2C2_SCL/OTG_HS_ULPI_NXT_45") (pintype "passive"))
    )
    (net (code "185") (name "unconnected-(U2-PH5{slash}I2C2_SDA{slash}SPI5_NSS{slash}FMC_SDNWE-Pad46)") (class "Default")
      (node (ref "U2") (pin "46") (pinfunction "PH5/I2C2_SDA/SPI5_NSS/FMC_SDNWE_46") (pintype "passive"))
    )
    (net (code "186") (name "unconnected-(U2-PH8{slash}I2C3_SDA{slash}FMC_D16{slash}DCMI_HSYNC{slash}LCD_R2-Pad85)") (class "Default")
      (node (ref "U2") (pin "85") (pinfunction "PH8/I2C3_SDA/FMC_D16/DCMI_HSYNC/LCD_R2_85") (pintype "passive"))
    )
    (net (code "187") (name "unconnected-(U2-PI11{slash}OTG_HS_ULPI_DIR-Pad13)") (class "Default")
      (node (ref "U2") (pin "13") (pinfunction "PI11/OTG_HS_ULPI_DIR_13") (pintype "passive"))
    )
    (net (code "188") (name "unconnected-(U5-NC-Pad3)") (class "Default")
      (node (ref "U5") (pin "3") (pinfunction "NC_3") (pintype "passive+no_connect"))
    )
    (net (code "189") (name "unconnected-(U9-GPIO0-Pad13)") (class "Default")
      (node (ref "U9") (pin "13") (pinfunction "GPIO0_13") (pintype "passive+no_connect"))
    )
    (net (code "190") (name "unconnected-(U9-GPIO1-Pad9)") (class "Default")
      (node (ref "U9") (pin "9") (pinfunction "GPIO1_9") (pintype "passive+no_connect"))
    )
    (net (code "191") (name "unconnected-(U9-GPIO2-Pad8)") (class "Default")
      (node (ref "U9") (pin "8") (pinfunction "GPIO2_8") (pintype "passive+no_connect"))
    )
    (net (code "192") (name "unconnected-(U9-GPIO3-Pad7)") (class "Default")
      (node (ref "U9") (pin "7") (pinfunction "GPIO3_7") (pintype "passive+no_connect"))
    )
    (net (code "193") (name "unconnected-(U9-TESTMD-Pad5)") (class "Default")
      (node (ref "U9") (pin "5") (pinfunction "TESTMD_5") (pintype "passive+no_connect"))
    )
  )
)
